# OpenDeck-r2_0_1.net
KiCad netlist of a schematic drawn in EAGLE
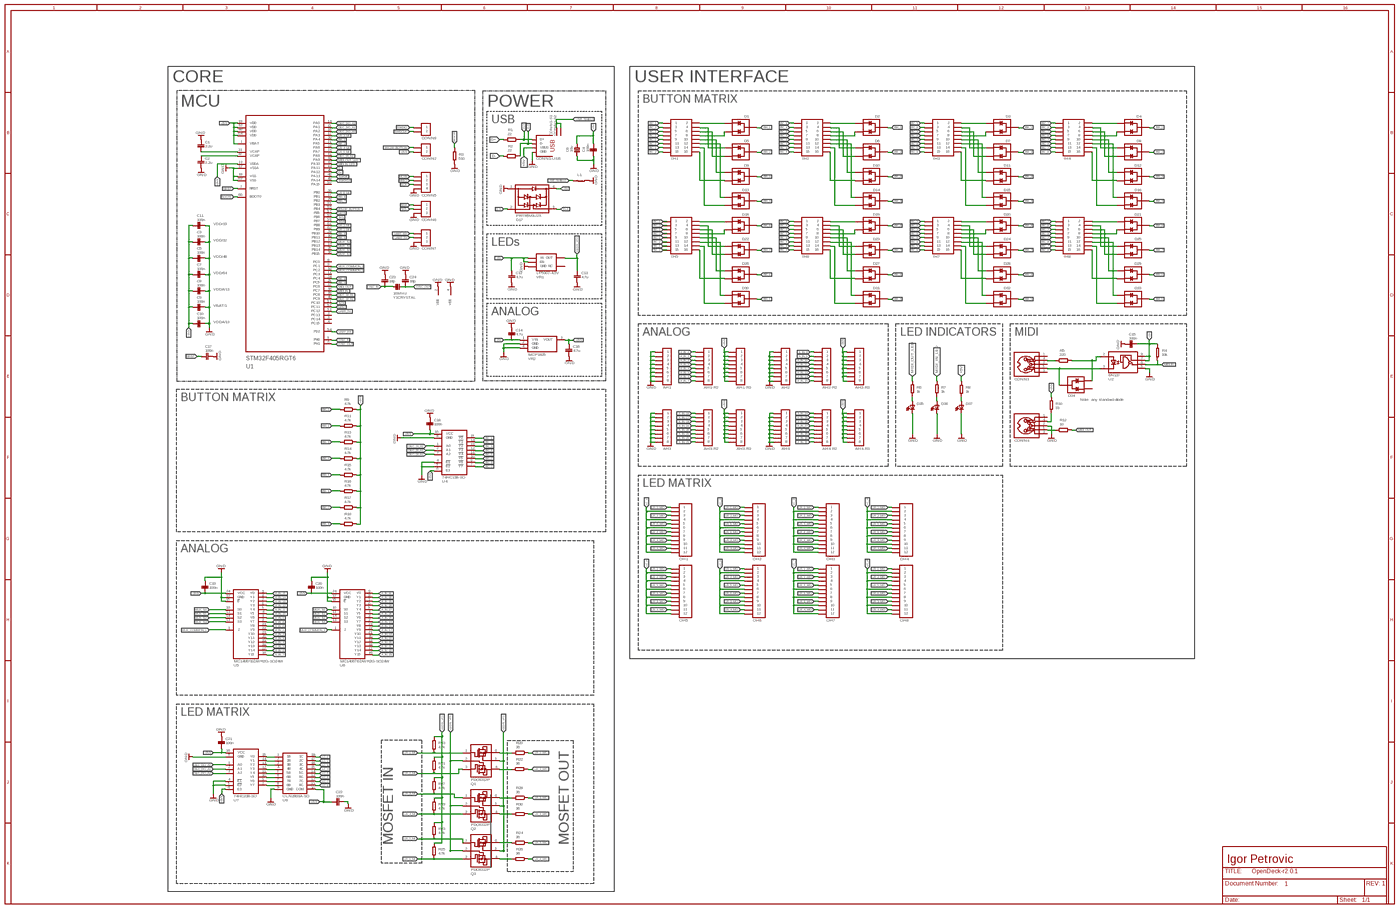
[diagram p0: schematic, sheet 1, overview]
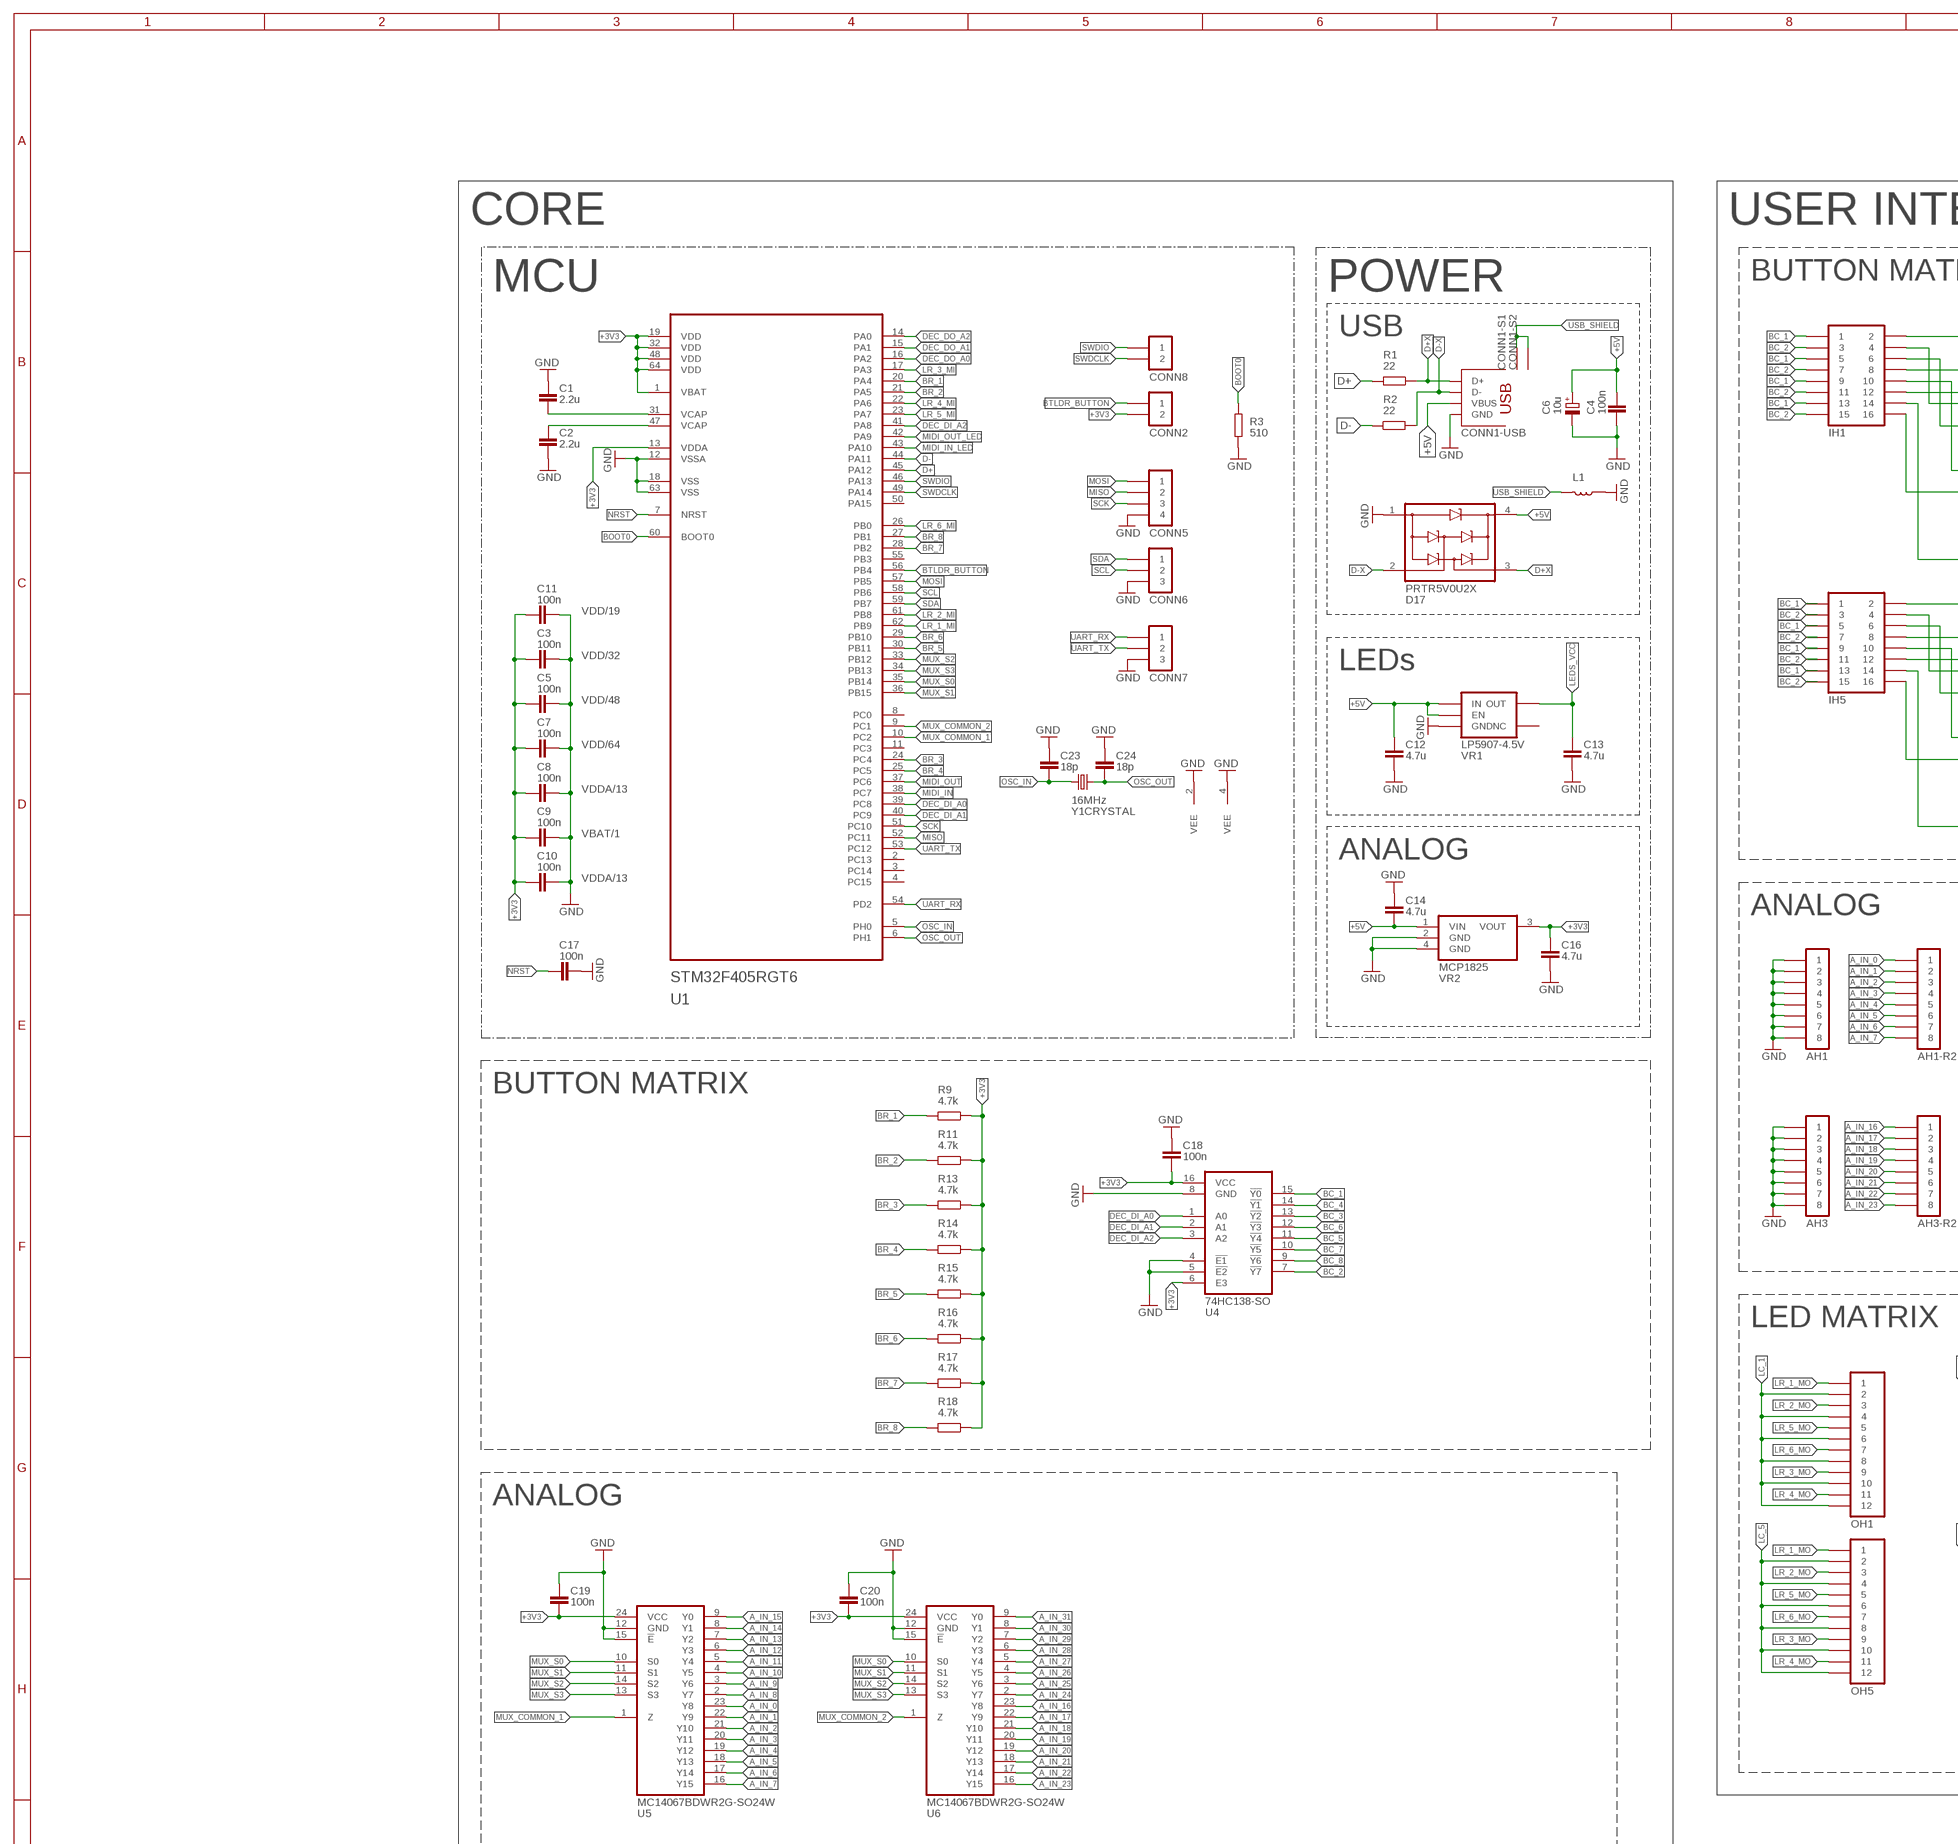
[diagram p1: schematic, sheet 1, part 1 of 4]
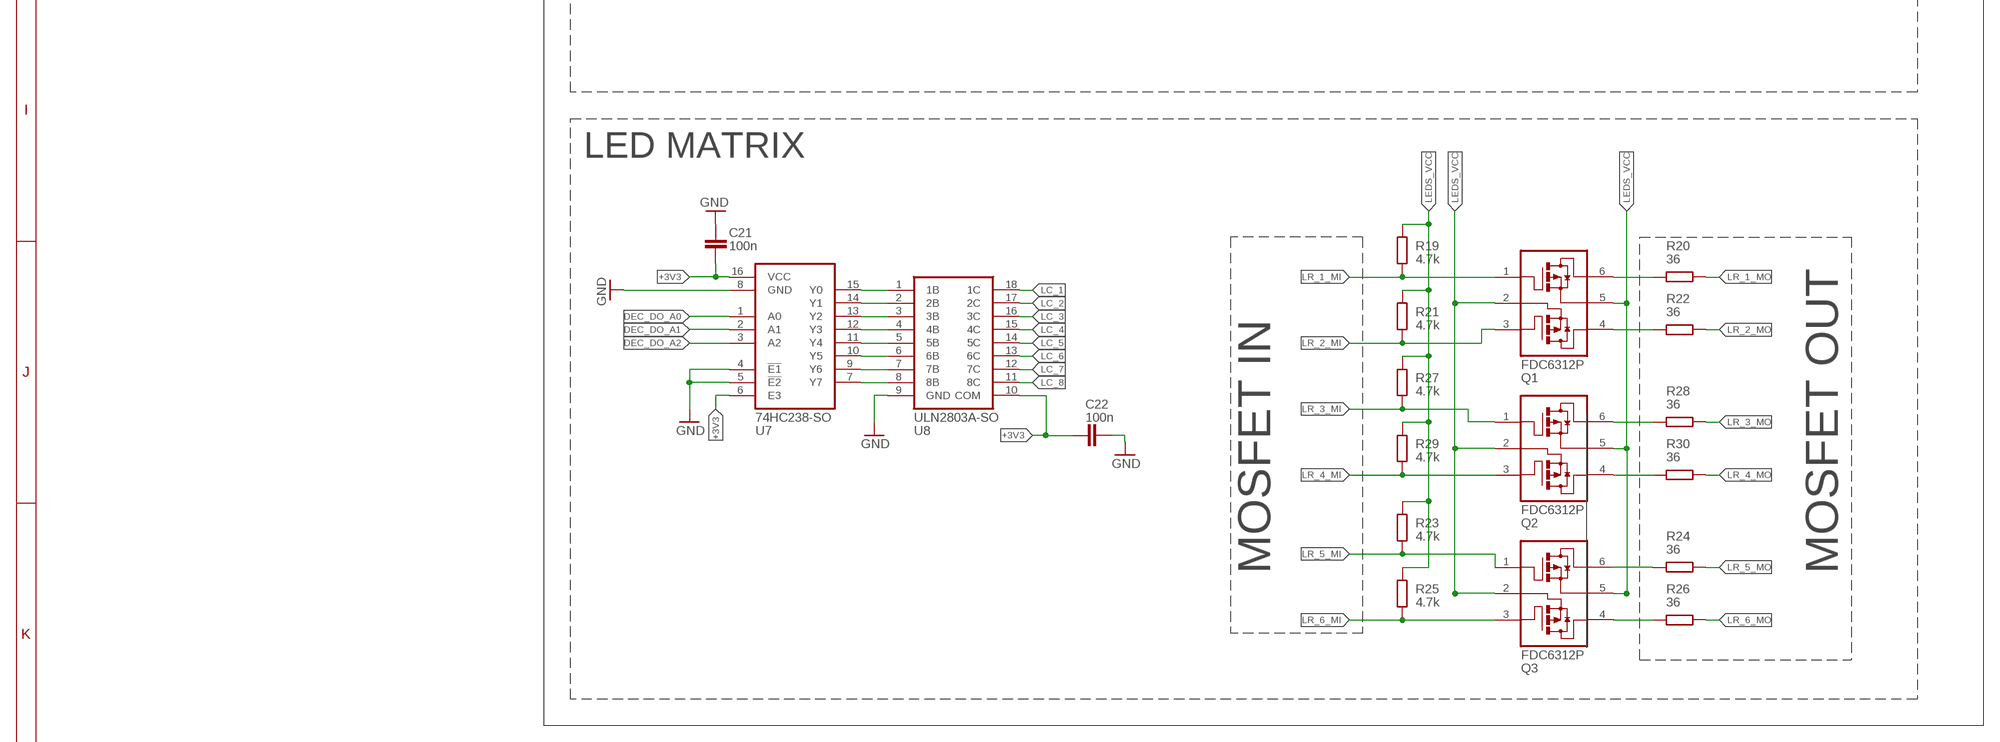
[diagram p2: schematic, sheet 1, part 2 of 4]
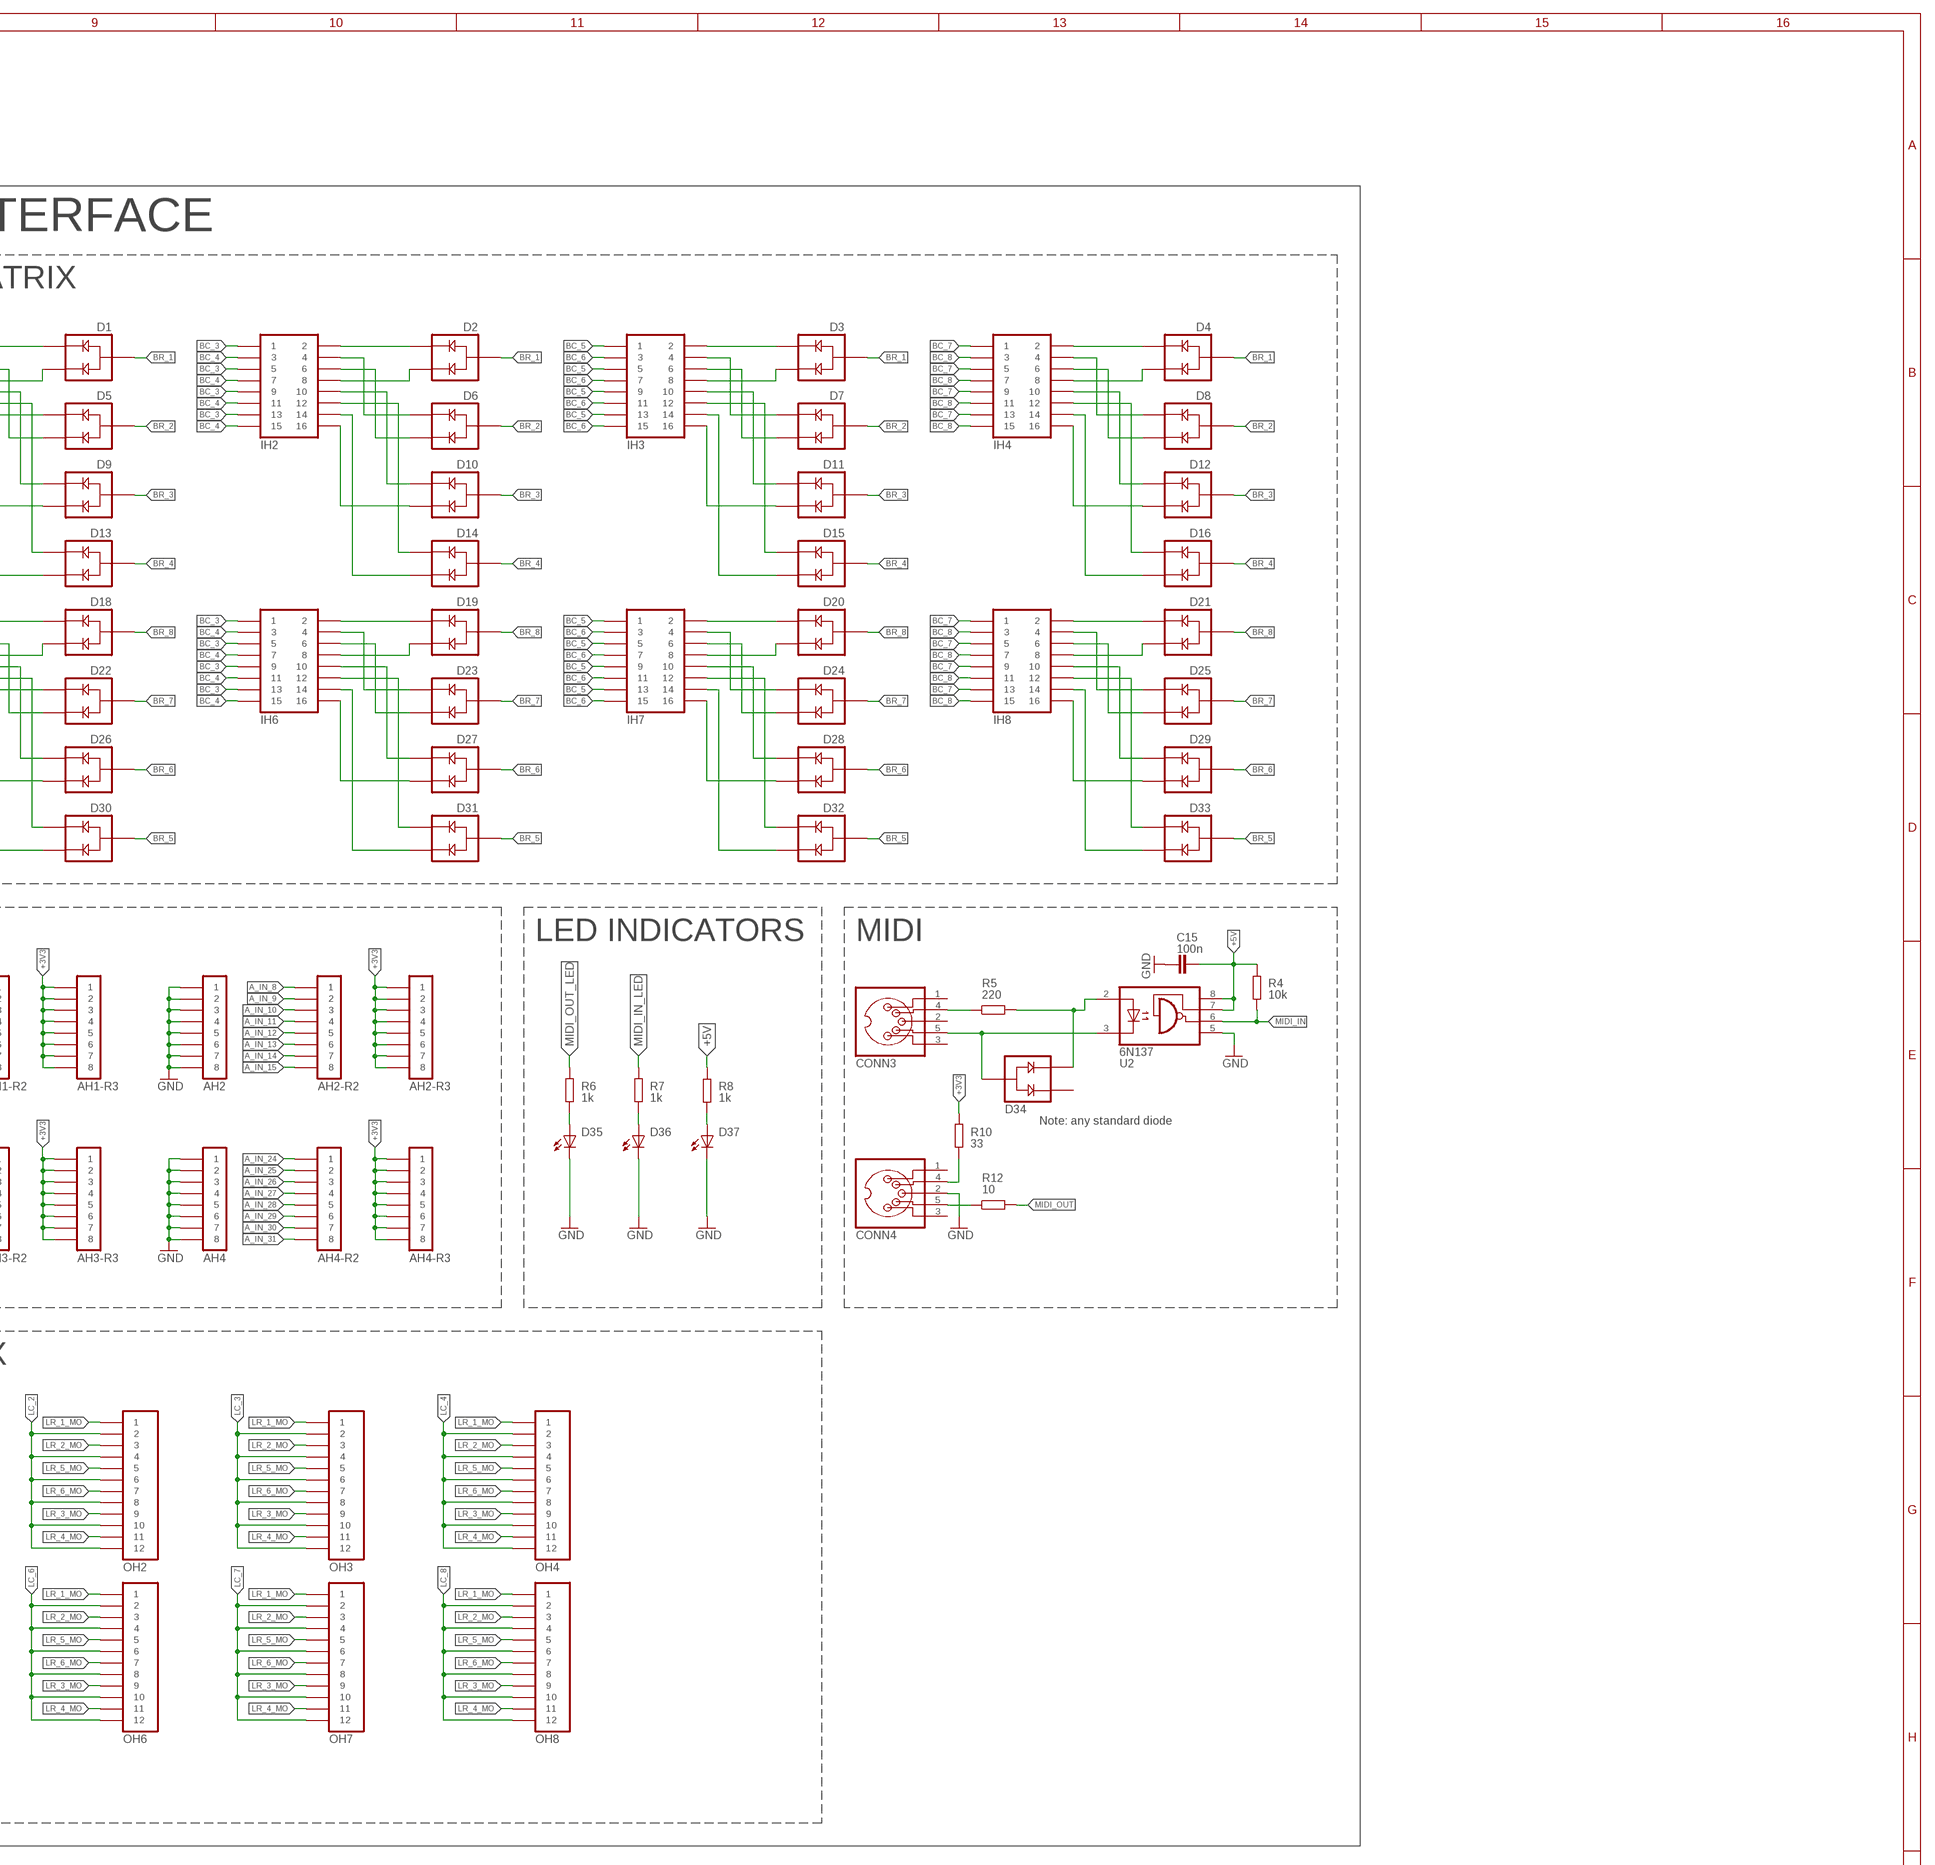
[diagram p3: schematic, sheet 1, part 3 of 4]
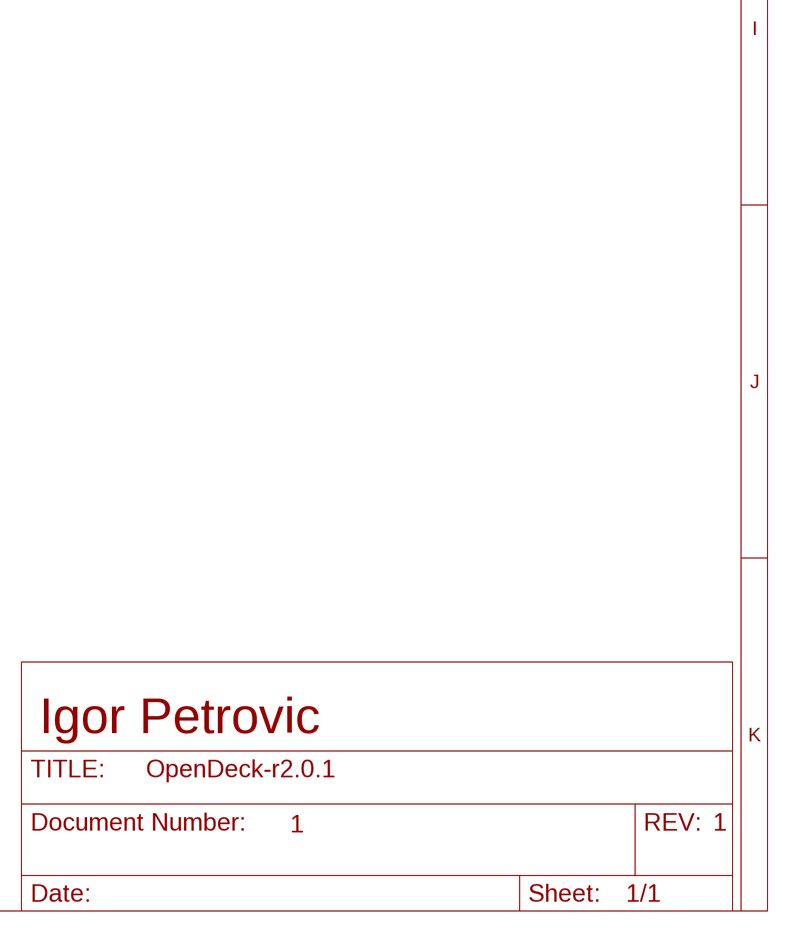
[diagram p4: schematic, sheet 1, part 4 of 4]

(export (version "E")
  (design (tool "Eeschema 10.0.6"))
  (components
    (comp (ref "AH1")
      (value "PINHD-3X08")
      (footprint "eagle-import:3X08-2.54")
      (libsource (lib "eagle-import") (part "PINHD-3X08"))
    )
    (comp (ref "AH2")
      (value "PINHD-3X08")
      (footprint "eagle-import:3X08-2.54")
      (libsource (lib "eagle-import") (part "PINHD-3X08"))
    )
    (comp (ref "AH3")
      (value "PINHD-3X08")
      (footprint "eagle-import:3X08-2.54")
      (libsource (lib "eagle-import") (part "PINHD-3X08"))
    )
    (comp (ref "AH4")
      (value "PINHD-3X08")
      (footprint "eagle-import:3X08-2.54")
      (libsource (lib "eagle-import") (part "PINHD-3X08"))
    )
    (comp (ref "C1")
      (value "2.2u")
      (footprint "eagle-import:C0402")
      (libsource (lib "eagle-import") (part "CAPACITOR-0402"))
    )
    (comp (ref "C2")
      (value "2.2u")
      (footprint "eagle-import:C0402")
      (libsource (lib "eagle-import") (part "CAPACITOR-0402"))
    )
    (comp (ref "C3")
      (value "100n")
      (footprint "eagle-import:C0402")
      (libsource (lib "eagle-import") (part "CAPACITOR-0402"))
    )
    (comp (ref "C4")
      (value "100n")
      (footprint "eagle-import:C0402")
      (libsource (lib "eagle-import") (part "CAPACITOR-0402"))
    )
    (comp (ref "C5")
      (value "100n")
      (footprint "eagle-import:C0402")
      (libsource (lib "eagle-import") (part "CAPACITOR-0402"))
    )
    (comp (ref "C6")
      (value "10u")
      (footprint "eagle-import:153CLV-0405")
      (fields (field (name "MANUFACTURER") "Multicomp") (field (name "MPN") "MCVVT016M100CA1L"))
      (libsource (lib "eagle-import") (part "ELECTROLYTIC_CAPACITOR-CLV-040516V"))
    )
    (comp (ref "C7")
      (value "100n")
      (footprint "eagle-import:C0402")
      (libsource (lib "eagle-import") (part "CAPACITOR-0402"))
    )
    (comp (ref "C8")
      (value "100n")
      (footprint "eagle-import:C0402")
      (libsource (lib "eagle-import") (part "CAPACITOR-0402"))
    )
    (comp (ref "C9")
      (value "100n")
      (footprint "eagle-import:C0402")
      (libsource (lib "eagle-import") (part "CAPACITOR-0402"))
    )
    (comp (ref "C10")
      (value "100n")
      (footprint "eagle-import:C0402")
      (libsource (lib "eagle-import") (part "CAPACITOR-0402"))
    )
    (comp (ref "C11")
      (value "100n")
      (footprint "eagle-import:C0402")
      (libsource (lib "eagle-import") (part "CAPACITOR-0402"))
    )
    (comp (ref "C12")
      (value "4.7u")
      (footprint "eagle-import:C0402")
      (libsource (lib "eagle-import") (part "CAPACITOR-0402"))
    )
    (comp (ref "C13")
      (value "4.7u")
      (footprint "eagle-import:C0402")
      (libsource (lib "eagle-import") (part "CAPACITOR-0402"))
    )
    (comp (ref "C14")
      (value "4.7u")
      (footprint "eagle-import:C0402")
      (libsource (lib "eagle-import") (part "CAPACITOR-0402"))
    )
    (comp (ref "C15")
      (value "100n")
      (footprint "eagle-import:C0402")
      (libsource (lib "eagle-import") (part "CAPACITOR-0402"))
    )
    (comp (ref "C16")
      (value "4.7u")
      (footprint "eagle-import:C0402")
      (libsource (lib "eagle-import") (part "CAPACITOR-0402"))
    )
    (comp (ref "C17")
      (value "100n")
      (footprint "eagle-import:C0402")
      (libsource (lib "eagle-import") (part "CAPACITOR-0402"))
    )
    (comp (ref "C18")
      (value "100n")
      (footprint "eagle-import:C0402")
      (libsource (lib "eagle-import") (part "CAPACITOR-0402"))
    )
    (comp (ref "C19")
      (value "100n")
      (footprint "eagle-import:C0402")
      (libsource (lib "eagle-import") (part "CAPACITOR-0402"))
    )
    (comp (ref "C20")
      (value "100n")
      (footprint "eagle-import:C0402")
      (libsource (lib "eagle-import") (part "CAPACITOR-0402"))
    )
    (comp (ref "C21")
      (value "100n")
      (footprint "eagle-import:C0402")
      (libsource (lib "eagle-import") (part "CAPACITOR-0402"))
    )
    (comp (ref "C22")
      (value "100n")
      (footprint "eagle-import:C0402")
      (libsource (lib "eagle-import") (part "CAPACITOR-0402"))
    )
    (comp (ref "C23")
      (value "18p")
      (footprint "eagle-import:C0402")
      (libsource (lib "eagle-import") (part "CAPACITOR-0402"))
    )
    (comp (ref "C24")
      (value "18p")
      (footprint "eagle-import:C0402")
      (libsource (lib "eagle-import") (part "CAPACITOR-0402"))
    )
    (comp (ref "CONN1")
      (value "USB-H")
      (footprint "eagle-import:USB-B-PTH")
      (libsource (lib "eagle-import") (part "USB-H"))
    )
    (comp (ref "CONN2")
      (value "PINHD-1X02-TH-2.54MM")
      (footprint "eagle-import:1X02-2.54-V")
      (libsource (lib "eagle-import") (part "PINHD-1X02-TH-2.54MM"))
    )
    (comp (ref "CONN3")
      (value "MIDI_CONN-STD")
      (footprint "eagle-import:DIN5_SUPPORT")
      (libsource (lib "eagle-import") (part "MIDI_CONN-STD"))
    )
    (comp (ref "CONN4")
      (value "MIDI_CONN-STD")
      (footprint "eagle-import:DIN5_SUPPORT")
      (libsource (lib "eagle-import") (part "MIDI_CONN-STD"))
    )
    (comp (ref "CONN5")
      (value "PINHD-1X04-TH-2.54MM")
      (footprint "eagle-import:1X04-2.54")
      (libsource (lib "eagle-import") (part "PINHD-1X04-TH-2.54MM"))
    )
    (comp (ref "CONN6")
      (value "PINHD-1X03-TH-2.54MM")
      (footprint "eagle-import:1X03-2.54-V")
      (libsource (lib "eagle-import") (part "PINHD-1X03-TH-2.54MM"))
    )
    (comp (ref "CONN7")
      (value "PINHD-1X03-TH-2.54MM")
      (footprint "eagle-import:1X03-2.54-V")
      (libsource (lib "eagle-import") (part "PINHD-1X03-TH-2.54MM"))
    )
    (comp (ref "CONN8")
      (value "PINHD-1X02-TH-2.54MM")
      (footprint "eagle-import:1X02-2.54-V")
      (libsource (lib "eagle-import") (part "PINHD-1X02-TH-2.54MM"))
    )
    (comp (ref "D1")
      (value "BAW56")
      (footprint "eagle-import:SOT23")
      (fields (field (name "MANUFACTURER") "Multicomp") (field (name "MPN") "BAW56-7-F"))
      (libsource (lib "eagle-import") (part "BAW56"))
    )
    (comp (ref "D2")
      (value "BAW56")
      (footprint "eagle-import:SOT23")
      (fields (field (name "MANUFACTURER") "Multicomp") (field (name "MPN") "BAW56-7-F"))
      (libsource (lib "eagle-import") (part "BAW56"))
    )
    (comp (ref "D3")
      (value "BAW56")
      (footprint "eagle-import:SOT23")
      (fields (field (name "MANUFACTURER") "Multicomp") (field (name "MPN") "BAW56-7-F"))
      (libsource (lib "eagle-import") (part "BAW56"))
    )
    (comp (ref "D4")
      (value "BAW56")
      (footprint "eagle-import:SOT23")
      (fields (field (name "MANUFACTURER") "Multicomp") (field (name "MPN") "BAW56-7-F"))
      (libsource (lib "eagle-import") (part "BAW56"))
    )
    (comp (ref "D5")
      (value "BAW56")
      (footprint "eagle-import:SOT23")
      (fields (field (name "MANUFACTURER") "Multicomp") (field (name "MPN") "BAW56-7-F"))
      (libsource (lib "eagle-import") (part "BAW56"))
    )
    (comp (ref "D6")
      (value "BAW56")
      (footprint "eagle-import:SOT23")
      (fields (field (name "MANUFACTURER") "Multicomp") (field (name "MPN") "BAW56-7-F"))
      (libsource (lib "eagle-import") (part "BAW56"))
    )
    (comp (ref "D7")
      (value "BAW56")
      (footprint "eagle-import:SOT23")
      (fields (field (name "MANUFACTURER") "Multicomp") (field (name "MPN") "BAW56-7-F"))
      (libsource (lib "eagle-import") (part "BAW56"))
    )
    (comp (ref "D8")
      (value "BAW56")
      (footprint "eagle-import:SOT23")
      (fields (field (name "MANUFACTURER") "Multicomp") (field (name "MPN") "BAW56-7-F"))
      (libsource (lib "eagle-import") (part "BAW56"))
    )
    (comp (ref "D9")
      (value "BAW56")
      (footprint "eagle-import:SOT23")
      (fields (field (name "MANUFACTURER") "Multicomp") (field (name "MPN") "BAW56-7-F"))
      (libsource (lib "eagle-import") (part "BAW56"))
    )
    (comp (ref "D10")
      (value "BAW56")
      (footprint "eagle-import:SOT23")
      (fields (field (name "MANUFACTURER") "Multicomp") (field (name "MPN") "BAW56-7-F"))
      (libsource (lib "eagle-import") (part "BAW56"))
    )
    (comp (ref "D11")
      (value "BAW56")
      (footprint "eagle-import:SOT23")
      (fields (field (name "MANUFACTURER") "Multicomp") (field (name "MPN") "BAW56-7-F"))
      (libsource (lib "eagle-import") (part "BAW56"))
    )
    (comp (ref "D12")
      (value "BAW56")
      (footprint "eagle-import:SOT23")
      (fields (field (name "MANUFACTURER") "Multicomp") (field (name "MPN") "BAW56-7-F"))
      (libsource (lib "eagle-import") (part "BAW56"))
    )
    (comp (ref "D13")
      (value "BAW56")
      (footprint "eagle-import:SOT23")
      (fields (field (name "MANUFACTURER") "Multicomp") (field (name "MPN") "BAW56-7-F"))
      (libsource (lib "eagle-import") (part "BAW56"))
    )
    (comp (ref "D14")
      (value "BAW56")
      (footprint "eagle-import:SOT23")
      (fields (field (name "MANUFACTURER") "Multicomp") (field (name "MPN") "BAW56-7-F"))
      (libsource (lib "eagle-import") (part "BAW56"))
    )
    (comp (ref "D15")
      (value "BAW56")
      (footprint "eagle-import:SOT23")
      (fields (field (name "MANUFACTURER") "Multicomp") (field (name "MPN") "BAW56-7-F"))
      (libsource (lib "eagle-import") (part "BAW56"))
    )
    (comp (ref "D16")
      (value "BAW56")
      (footprint "eagle-import:SOT23")
      (fields (field (name "MANUFACTURER") "Multicomp") (field (name "MPN") "BAW56-7-F"))
      (libsource (lib "eagle-import") (part "BAW56"))
    )
    (comp (ref "D17")
      (value "PRTR5V0U2X")
      (footprint "eagle-import:SOT143")
      (fields (field (name "MANUFACTURER") "Nexperia"))
      (libsource (lib "eagle-import") (part "PRTR5V0U2X"))
    )
    (comp (ref "D18")
      (value "BAW56")
      (footprint "eagle-import:SOT23")
      (fields (field (name "MANUFACTURER") "Multicomp") (field (name "MPN") "BAW56-7-F"))
      (libsource (lib "eagle-import") (part "BAW56"))
    )
    (comp (ref "D19")
      (value "BAW56")
      (footprint "eagle-import:SOT23")
      (fields (field (name "MANUFACTURER") "Multicomp") (field (name "MPN") "BAW56-7-F"))
      (libsource (lib "eagle-import") (part "BAW56"))
    )
    (comp (ref "D20")
      (value "BAW56")
      (footprint "eagle-import:SOT23")
      (fields (field (name "MANUFACTURER") "Multicomp") (field (name "MPN") "BAW56-7-F"))
      (libsource (lib "eagle-import") (part "BAW56"))
    )
    (comp (ref "D21")
      (value "BAW56")
      (footprint "eagle-import:SOT23")
      (fields (field (name "MANUFACTURER") "Multicomp") (field (name "MPN") "BAW56-7-F"))
      (libsource (lib "eagle-import") (part "BAW56"))
    )
    (comp (ref "D22")
      (value "BAW56")
      (footprint "eagle-import:SOT23")
      (fields (field (name "MANUFACTURER") "Multicomp") (field (name "MPN") "BAW56-7-F"))
      (libsource (lib "eagle-import") (part "BAW56"))
    )
    (comp (ref "D23")
      (value "BAW56")
      (footprint "eagle-import:SOT23")
      (fields (field (name "MANUFACTURER") "Multicomp") (field (name "MPN") "BAW56-7-F"))
      (libsource (lib "eagle-import") (part "BAW56"))
    )
    (comp (ref "D24")
      (value "BAW56")
      (footprint "eagle-import:SOT23")
      (fields (field (name "MANUFACTURER") "Multicomp") (field (name "MPN") "BAW56-7-F"))
      (libsource (lib "eagle-import") (part "BAW56"))
    )
    (comp (ref "D25")
      (value "BAW56")
      (footprint "eagle-import:SOT23")
      (fields (field (name "MANUFACTURER") "Multicomp") (field (name "MPN") "BAW56-7-F"))
      (libsource (lib "eagle-import") (part "BAW56"))
    )
    (comp (ref "D26")
      (value "BAW56")
      (footprint "eagle-import:SOT23")
      (fields (field (name "MANUFACTURER") "Multicomp") (field (name "MPN") "BAW56-7-F"))
      (libsource (lib "eagle-import") (part "BAW56"))
    )
    (comp (ref "D27")
      (value "BAW56")
      (footprint "eagle-import:SOT23")
      (fields (field (name "MANUFACTURER") "Multicomp") (field (name "MPN") "BAW56-7-F"))
      (libsource (lib "eagle-import") (part "BAW56"))
    )
    (comp (ref "D28")
      (value "BAW56")
      (footprint "eagle-import:SOT23")
      (fields (field (name "MANUFACTURER") "Multicomp") (field (name "MPN") "BAW56-7-F"))
      (libsource (lib "eagle-import") (part "BAW56"))
    )
    (comp (ref "D29")
      (value "BAW56")
      (footprint "eagle-import:SOT23")
      (fields (field (name "MANUFACTURER") "Multicomp") (field (name "MPN") "BAW56-7-F"))
      (libsource (lib "eagle-import") (part "BAW56"))
    )
    (comp (ref "D30")
      (value "BAW56")
      (footprint "eagle-import:SOT23")
      (fields (field (name "MANUFACTURER") "Multicomp") (field (name "MPN") "BAW56-7-F"))
      (libsource (lib "eagle-import") (part "BAW56"))
    )
    (comp (ref "D31")
      (value "BAW56")
      (footprint "eagle-import:SOT23")
      (fields (field (name "MANUFACTURER") "Multicomp") (field (name "MPN") "BAW56-7-F"))
      (libsource (lib "eagle-import") (part "BAW56"))
    )
    (comp (ref "D32")
      (value "BAW56")
      (footprint "eagle-import:SOT23")
      (fields (field (name "MANUFACTURER") "Multicomp") (field (name "MPN") "BAW56-7-F"))
      (libsource (lib "eagle-import") (part "BAW56"))
    )
    (comp (ref "D33")
      (value "BAW56")
      (footprint "eagle-import:SOT23")
      (fields (field (name "MANUFACTURER") "Multicomp") (field (name "MPN") "BAW56-7-F"))
      (libsource (lib "eagle-import") (part "BAW56"))
    )
    (comp (ref "D34")
      (value "BAW56")
      (footprint "eagle-import:SOT23")
      (fields (field (name "MANUFACTURER") "Multicomp") (field (name "MPN") "BAW56-7-F"))
      (libsource (lib "eagle-import") (part "BAW56"))
    )
    (comp (ref "D35")
      (value "Red")
      (footprint "eagle-import:0805_LED")
      (libsource (lib "eagle-import") (part "LED-0805"))
    )
    (comp (ref "D36")
      (value "Yellow")
      (footprint "eagle-import:0805_LED")
      (libsource (lib "eagle-import") (part "LED-0805"))
    )
    (comp (ref "D37")
      (value "Green")
      (footprint "eagle-import:0805_LED")
      (libsource (lib "eagle-import") (part "LED-0805"))
    )
    (comp (ref "IH1")
      (value "PINHD-2X08-TH-2.54MM")
      (footprint "eagle-import:2X08-2.54")
      (libsource (lib "eagle-import") (part "PINHD-2X08-TH-2.54MM"))
    )
    (comp (ref "IH2")
      (value "PINHD-2X08-TH-2.54MM")
      (footprint "eagle-import:2X08-2.54")
      (libsource (lib "eagle-import") (part "PINHD-2X08-TH-2.54MM"))
    )
    (comp (ref "IH3")
      (value "PINHD-2X08-TH-2.54MM")
      (footprint "eagle-import:2X08-2.54")
      (libsource (lib "eagle-import") (part "PINHD-2X08-TH-2.54MM"))
    )
    (comp (ref "IH4")
      (value "PINHD-2X08-TH-2.54MM")
      (footprint "eagle-import:2X08-2.54")
      (libsource (lib "eagle-import") (part "PINHD-2X08-TH-2.54MM"))
    )
    (comp (ref "IH5")
      (value "PINHD-2X08-TH-2.54MM")
      (footprint "eagle-import:2X08-2.54")
      (libsource (lib "eagle-import") (part "PINHD-2X08-TH-2.54MM"))
    )
    (comp (ref "IH6")
      (value "PINHD-2X08-TH-2.54MM")
      (footprint "eagle-import:2X08-2.54")
      (libsource (lib "eagle-import") (part "PINHD-2X08-TH-2.54MM"))
    )
    (comp (ref "IH7")
      (value "PINHD-2X08-TH-2.54MM")
      (footprint "eagle-import:2X08-2.54")
      (libsource (lib "eagle-import") (part "PINHD-2X08-TH-2.54MM"))
    )
    (comp (ref "IH8")
      (value "PINHD-2X08-TH-2.54MM")
      (footprint "eagle-import:2X08-2.54")
      (libsource (lib "eagle-import") (part "PINHD-2X08-TH-2.54MM"))
    )
    (comp (ref "L1")
      (value "FERRITE_BEAD-BLM21PG221SN1D")
      (footprint "eagle-import:L0805")
      (fields (field (name "MANUFACTURER") "Murata") (field (name "MPN") "BLM21PG221SN1D"))
      (libsource (lib "eagle-import") (part "FERRITE_BEAD-BLM21PG221SN1D"))
    )
    (comp (ref "OH1")
      (value "PINHD-2X06-TH-2.54MM")
      (footprint "eagle-import:2X06-2.54-V")
      (libsource (lib "eagle-import") (part "PINHD-2X06-TH-2.54MM"))
    )
    (comp (ref "OH2")
      (value "PINHD-2X06-TH-2.54MM")
      (footprint "eagle-import:2X06-2.54-V")
      (libsource (lib "eagle-import") (part "PINHD-2X06-TH-2.54MM"))
    )
    (comp (ref "OH3")
      (value "PINHD-2X06-TH-2.54MM")
      (footprint "eagle-import:2X06-2.54-V")
      (libsource (lib "eagle-import") (part "PINHD-2X06-TH-2.54MM"))
    )
    (comp (ref "OH4")
      (value "PINHD-2X06-TH-2.54MM")
      (footprint "eagle-import:2X06-2.54-V")
      (libsource (lib "eagle-import") (part "PINHD-2X06-TH-2.54MM"))
    )
    (comp (ref "OH5")
      (value "PINHD-2X06-TH-2.54MM")
      (footprint "eagle-import:2X06-2.54-V")
      (libsource (lib "eagle-import") (part "PINHD-2X06-TH-2.54MM"))
    )
    (comp (ref "OH6")
      (value "PINHD-2X06-TH-2.54MM")
      (footprint "eagle-import:2X06-2.54-V")
      (libsource (lib "eagle-import") (part "PINHD-2X06-TH-2.54MM"))
    )
    (comp (ref "OH7")
      (value "PINHD-2X06-TH-2.54MM")
      (footprint "eagle-import:2X06-2.54-V")
      (libsource (lib "eagle-import") (part "PINHD-2X06-TH-2.54MM"))
    )
    (comp (ref "OH8")
      (value "PINHD-2X06-TH-2.54MM")
      (footprint "eagle-import:2X06-2.54-V")
      (libsource (lib "eagle-import") (part "PINHD-2X06-TH-2.54MM"))
    )
    (comp (ref "Q1")
      (value "FDC6312P")
      (footprint "eagle-import:SSOT6")
      (fields (field (name "MANUFACTURER") "ON Semiconductor"))
      (libsource (lib "eagle-import") (part "FDC6312P"))
    )
    (comp (ref "Q2")
      (value "FDC6312P")
      (footprint "eagle-import:SSOT6")
      (fields (field (name "MANUFACTURER") "ON Semiconductor"))
      (libsource (lib "eagle-import") (part "FDC6312P"))
    )
    (comp (ref "Q3")
      (value "FDC6312P")
      (footprint "eagle-import:SSOT6")
      (fields (field (name "MANUFACTURER") "ON Semiconductor"))
      (libsource (lib "eagle-import") (part "FDC6312P"))
    )
    (comp (ref "R1")
      (value "22")
      (footprint "eagle-import:R0402")
      (libsource (lib "eagle-import") (part "RESISTOR-0402"))
    )
    (comp (ref "R2")
      (value "22")
      (footprint "eagle-import:R0402")
      (libsource (lib "eagle-import") (part "RESISTOR-0402"))
    )
    (comp (ref "R3")
      (value "510")
      (footprint "eagle-import:R0402")
      (libsource (lib "eagle-import") (part "RESISTOR-0402"))
    )
    (comp (ref "R4")
      (value "10k")
      (footprint "eagle-import:R0402")
      (libsource (lib "eagle-import") (part "RESISTOR-0402"))
    )
    (comp (ref "R5")
      (value "220")
      (footprint "eagle-import:R0402")
      (libsource (lib "eagle-import") (part "RESISTOR-0402"))
    )
    (comp (ref "R6")
      (value "1k")
      (footprint "eagle-import:R0402")
      (libsource (lib "eagle-import") (part "RESISTOR-0402"))
    )
    (comp (ref "R7")
      (value "1k")
      (footprint "eagle-import:R0402")
      (libsource (lib "eagle-import") (part "RESISTOR-0402"))
    )
    (comp (ref "R8")
      (value "1k")
      (footprint "eagle-import:R0402")
      (libsource (lib "eagle-import") (part "RESISTOR-0402"))
    )
    (comp (ref "R9")
      (value "4.7k")
      (footprint "eagle-import:R0402")
      (libsource (lib "eagle-import") (part "RESISTOR-0402"))
    )
    (comp (ref "R10")
      (value "33")
      (footprint "eagle-import:R0402")
      (libsource (lib "eagle-import") (part "RESISTOR-0402"))
    )
    (comp (ref "R11")
      (value "4.7k")
      (footprint "eagle-import:R0402")
      (libsource (lib "eagle-import") (part "RESISTOR-0402"))
    )
    (comp (ref "R12")
      (value "10")
      (footprint "eagle-import:R0402")
      (libsource (lib "eagle-import") (part "RESISTOR-0402"))
    )
    (comp (ref "R13")
      (value "4.7k")
      (footprint "eagle-import:R0402")
      (libsource (lib "eagle-import") (part "RESISTOR-0402"))
    )
    (comp (ref "R14")
      (value "4.7k")
      (footprint "eagle-import:R0402")
      (libsource (lib "eagle-import") (part "RESISTOR-0402"))
    )
    (comp (ref "R15")
      (value "4.7k")
      (footprint "eagle-import:R0402")
      (libsource (lib "eagle-import") (part "RESISTOR-0402"))
    )
    (comp (ref "R16")
      (value "4.7k")
      (footprint "eagle-import:R0402")
      (libsource (lib "eagle-import") (part "RESISTOR-0402"))
    )
    (comp (ref "R17")
      (value "4.7k")
      (footprint "eagle-import:R0402")
      (libsource (lib "eagle-import") (part "RESISTOR-0402"))
    )
    (comp (ref "R18")
      (value "4.7k")
      (footprint "eagle-import:R0402")
      (libsource (lib "eagle-import") (part "RESISTOR-0402"))
    )
    (comp (ref "R19")
      (value "4.7k")
      (footprint "eagle-import:R0402")
      (libsource (lib "eagle-import") (part "RESISTOR-0402"))
    )
    (comp (ref "R20")
      (value "36")
      (footprint "eagle-import:R0402")
      (libsource (lib "eagle-import") (part "RESISTOR-0402"))
    )
    (comp (ref "R21")
      (value "4.7k")
      (footprint "eagle-import:R0402")
      (libsource (lib "eagle-import") (part "RESISTOR-0402"))
    )
    (comp (ref "R22")
      (value "36")
      (footprint "eagle-import:R0402")
      (libsource (lib "eagle-import") (part "RESISTOR-0402"))
    )
    (comp (ref "R23")
      (value "4.7k")
      (footprint "eagle-import:R0402")
      (libsource (lib "eagle-import") (part "RESISTOR-0402"))
    )
    (comp (ref "R24")
      (value "36")
      (footprint "eagle-import:R0402")
      (libsource (lib "eagle-import") (part "RESISTOR-0402"))
    )
    (comp (ref "R25")
      (value "4.7k")
      (footprint "eagle-import:R0402")
      (libsource (lib "eagle-import") (part "RESISTOR-0402"))
    )
    (comp (ref "R26")
      (value "36")
      (footprint "eagle-import:R0402")
      (libsource (lib "eagle-import") (part "RESISTOR-0402"))
    )
    (comp (ref "R27")
      (value "4.7k")
      (footprint "eagle-import:R0402")
      (libsource (lib "eagle-import") (part "RESISTOR-0402"))
    )
    (comp (ref "R28")
      (value "36")
      (footprint "eagle-import:R0402")
      (libsource (lib "eagle-import") (part "RESISTOR-0402"))
    )
    (comp (ref "R29")
      (value "4.7k")
      (footprint "eagle-import:R0402")
      (libsource (lib "eagle-import") (part "RESISTOR-0402"))
    )
    (comp (ref "R30")
      (value "36")
      (footprint "eagle-import:R0402")
      (libsource (lib "eagle-import") (part "RESISTOR-0402"))
    )
    (comp (ref "U1")
      (value "STM32F405RGT6")
      (footprint "eagle-import:TQFP-64-10X10")
      (fields (field (name "MANUFACTURER") "ST Microelectronics"))
      (libsource (lib "eagle-import") (part "STM32F405RGT6"))
    )
    (comp (ref "U2")
      (value "6N137")
      (footprint "eagle-import:DIL08")
      (fields (field (name "MANUFACTURER") "Vishay"))
      (libsource (lib "eagle-import") (part "6N137"))
    )
    (comp (ref "U4")
      (value "74HC138-SO")
      (footprint "eagle-import:SO16")
      (fields (field (name "MANUFACTURER") "Nexperia") (field (name "MPN") "74HC138D"))
      (libsource (lib "eagle-import") (part "74138-SOHC"))
    )
    (comp (ref "U5")
      (value "MC14067BDWR2G-SO24W")
      (footprint "eagle-import:SO24-W")
      (fields (field (name "MANUFACTURER") "ON Semiconductor") (field (name "MPN") "MC14067BDWR2G"))
      (libsource (lib "eagle-import") (part "MC14067BDWR2G-SO24W"))
    )
    (comp (ref "U6")
      (value "MC14067BDWR2G-SO24W")
      (footprint "eagle-import:SO24-W")
      (fields (field (name "MANUFACTURER") "ON Semiconductor") (field (name "MPN") "MC14067BDWR2G"))
      (libsource (lib "eagle-import") (part "MC14067BDWR2G-SO24W"))
    )
    (comp (ref "U7")
      (value "74HC238-SO")
      (footprint "eagle-import:SO16")
      (fields (field (name "MANUFACTURER") "Nexperia") (field (name "MPN") "74HC238D"))
      (libsource (lib "eagle-import") (part "74238-SOHC"))
    )
    (comp (ref "U8")
      (value "ULN2803A-SO")
      (footprint "eagle-import:SO18")
      (fields (field (name "MANUFACTURER") "Texas Instruments") (field (name "MPN") "ULN2803ADWR"))
      (libsource (lib "eagle-import") (part "ULN2803A-SO"))
    )
    (comp (ref "VR1")
      (value "LP5907-4.5V")
      (footprint "eagle-import:SOT23-5")
      (fields (field (name "MANUFACTURER") "Texas Instruments") (field (name "MPN") "LP5907MFX-4.5/NOPB"))
      (libsource (lib "eagle-import") (part "LP5907-4.5V"))
    )
    (comp (ref "VR2")
      (value "MCP1825")
      (footprint "eagle-import:SOT223")
      (fields (field (name "MANUFACTURER") "Microchip") (field (name "MPN") "MCP1825S-3302E/DB"))
      (libsource (lib "eagle-import") (part "MCP1825"))
    )
    (comp (ref "Y1")
      (value "16MHz")
      (footprint "eagle-import:CRYSTAL-SMD-2.5X2")
      (fields (field (name "MANUFACTURER") "TXC") (field (name "MPN") "8Z-16.000MEEQ-T"))
      (libsource (lib "eagle-import") (part "CRYSTAL-4P-SMD-2.5X2"))
    )
  )
  (nets
    (net (code "1") (name "+3V3") (class "Default")
      (node (ref "AH1") (pin "12") (pinfunction "4_12") (pintype "passive"))
      (node (ref "AH1") (pin "15") (pinfunction "5_15") (pintype "passive"))
      (node (ref "AH1") (pin "18") (pinfunction "6_18") (pintype "passive"))
      (node (ref "AH1") (pin "21") (pinfunction "7_21") (pintype "passive"))
      (node (ref "AH1") (pin "24") (pinfunction "8_24") (pintype "passive"))
      (node (ref "AH1") (pin "3") (pinfunction "1_3") (pintype "passive"))
      (node (ref "AH1") (pin "6") (pinfunction "2_6") (pintype "passive"))
      (node (ref "AH1") (pin "9") (pinfunction "3_9") (pintype "passive"))
      (node (ref "AH2") (pin "12") (pinfunction "4_12") (pintype "passive"))
      (node (ref "AH2") (pin "15") (pinfunction "5_15") (pintype "passive"))
      (node (ref "AH2") (pin "18") (pinfunction "6_18") (pintype "passive"))
      (node (ref "AH2") (pin "21") (pinfunction "7_21") (pintype "passive"))
      (node (ref "AH2") (pin "24") (pinfunction "8_24") (pintype "passive"))
      (node (ref "AH2") (pin "3") (pinfunction "1_3") (pintype "passive"))
      (node (ref "AH2") (pin "6") (pinfunction "2_6") (pintype "passive"))
      (node (ref "AH2") (pin "9") (pinfunction "3_9") (pintype "passive"))
      (node (ref "AH3") (pin "12") (pinfunction "4_12") (pintype "passive"))
      (node (ref "AH3") (pin "15") (pinfunction "5_15") (pintype "passive"))
      (node (ref "AH3") (pin "18") (pinfunction "6_18") (pintype "passive"))
      (node (ref "AH3") (pin "21") (pinfunction "7_21") (pintype "passive"))
      (node (ref "AH3") (pin "24") (pinfunction "8_24") (pintype "passive"))
      (node (ref "AH3") (pin "3") (pinfunction "1_3") (pintype "passive"))
      (node (ref "AH3") (pin "6") (pinfunction "2_6") (pintype "passive"))
      (node (ref "AH3") (pin "9") (pinfunction "3_9") (pintype "passive"))
      (node (ref "AH4") (pin "12") (pinfunction "4_12") (pintype "passive"))
      (node (ref "AH4") (pin "15") (pinfunction "5_15") (pintype "passive"))
      (node (ref "AH4") (pin "18") (pinfunction "6_18") (pintype "passive"))
      (node (ref "AH4") (pin "21") (pinfunction "7_21") (pintype "passive"))
      (node (ref "AH4") (pin "24") (pinfunction "8_24") (pintype "passive"))
      (node (ref "AH4") (pin "3") (pinfunction "1_3") (pintype "passive"))
      (node (ref "AH4") (pin "6") (pinfunction "2_6") (pintype "passive"))
      (node (ref "AH4") (pin "9") (pinfunction "3_9") (pintype "passive"))
      (node (ref "C10") (pin "1") (pinfunction "1_1") (pintype "passive"))
      (node (ref "C11") (pin "1") (pinfunction "1_1") (pintype "passive"))
      (node (ref "C16") (pin "1") (pinfunction "1_1") (pintype "passive"))
      (node (ref "C18") (pin "2") (pinfunction "2_2") (pintype "passive"))
      (node (ref "C19") (pin "2") (pinfunction "2_2") (pintype "passive"))
      (node (ref "C20") (pin "2") (pinfunction "2_2") (pintype "passive"))
      (node (ref "C21") (pin "1") (pinfunction "1_1") (pintype "passive"))
      (node (ref "C22") (pin "1") (pinfunction "1_1") (pintype "passive"))
      (node (ref "C3") (pin "1") (pinfunction "1_1") (pintype "passive"))
      (node (ref "C5") (pin "1") (pinfunction "1_1") (pintype "passive"))
      (node (ref "C7") (pin "1") (pinfunction "1_1") (pintype "passive"))
      (node (ref "C8") (pin "1") (pinfunction "1_1") (pintype "passive"))
      (node (ref "C9") (pin "1") (pinfunction "1_1") (pintype "passive"))
      (node (ref "CONN2") (pin "2") (pinfunction "2_2") (pintype "passive"))
      (node (ref "R10") (pin "2") (pinfunction "2_2") (pintype "passive"))
      (node (ref "R11") (pin "1") (pinfunction "1_1") (pintype "passive"))
      (node (ref "R13") (pin "1") (pinfunction "1_1") (pintype "passive"))
      (node (ref "R14") (pin "1") (pinfunction "1_1") (pintype "passive"))
      (node (ref "R15") (pin "1") (pinfunction "1_1") (pintype "passive"))
      (node (ref "R16") (pin "1") (pinfunction "1_1") (pintype "passive"))
      (node (ref "R17") (pin "1") (pinfunction "1_1") (pintype "passive"))
      (node (ref "R18") (pin "1") (pinfunction "1_1") (pintype "passive"))
      (node (ref "R9") (pin "1") (pinfunction "1_1") (pintype "passive"))
      (node (ref "U1") (pin "1") (pinfunction "VBAT_1") (pintype "bidirectional"))
      (node (ref "U1") (pin "13") (pinfunction "VDDA_13") (pintype "bidirectional"))
      (node (ref "U1") (pin "19") (pinfunction "VDD_19") (pintype "bidirectional"))
      (node (ref "U1") (pin "32") (pinfunction "VDD_32") (pintype "bidirectional"))
      (node (ref "U1") (pin "48") (pinfunction "VDD_48") (pintype "bidirectional"))
      (node (ref "U1") (pin "64") (pinfunction "VDD_64") (pintype "bidirectional"))
      (node (ref "U4") (pin "16") (pinfunction "VCC_16") (pintype "power_in"))
      (node (ref "U4") (pin "6") (pinfunction "E3_6") (pintype "input"))
      (node (ref "U5") (pin "24") (pinfunction "VCC_24") (pintype "passive"))
      (node (ref "U6") (pin "24") (pinfunction "VCC_24") (pintype "passive"))
      (node (ref "U7") (pin "16") (pinfunction "VCC_16") (pintype "power_in"))
      (node (ref "U7") (pin "6") (pinfunction "E3_6") (pintype "input"))
      (node (ref "U8") (pin "10") (pinfunction "COM_10") (pintype "passive"))
      (node (ref "VR2") (pin "3") (pinfunction "VOUT_3") (pintype "passive"))
    )
    (net (code "2") (name "+5V") (class "Default")
      (node (ref "C12") (pin "1") (pinfunction "1_1") (pintype "passive"))
      (node (ref "C14") (pin "1") (pinfunction "1_1") (pintype "passive"))
      (node (ref "C15") (pin "2") (pinfunction "2_2") (pintype "passive"))
      (node (ref "C4") (pin "2") (pinfunction "2_2") (pintype "passive"))
      (node (ref "C6") (pin "+") (pinfunction "+_+") (pintype "passive"))
      (node (ref "CONN1") (pin "VBUS") (pinfunction "VBUS_VBUS") (pintype "bidirectional"))
      (node (ref "D17") (pin "4") (pinfunction "VCC_4") (pintype "passive"))
      (node (ref "R4") (pin "1") (pinfunction "1_1") (pintype "passive"))
      (node (ref "R8") (pin "1") (pinfunction "1_1") (pintype "passive"))
      (node (ref "U2") (pin "7") (pinfunction "VE_7") (pintype "input"))
      (node (ref "U2") (pin "8") (pinfunction "VCC_8") (pintype "power_in"))
      (node (ref "VR1") (pin "1") (pinfunction "IN_1") (pintype "power_in"))
      (node (ref "VR1") (pin "3") (pinfunction "EN_3") (pintype "input"))
      (node (ref "VR2") (pin "1") (pinfunction "VIN_1") (pintype "passive"))
    )
    (net (code "3") (name "A_IN_0") (class "Default")
      (node (ref "AH1") (pin "2") (pinfunction "1_2") (pintype "passive"))
      (node (ref "U5") (pin "23") (pinfunction "Y8_23") (pintype "bidirectional"))
    )
    (net (code "4") (name "A_IN_1") (class "Default")
      (node (ref "AH1") (pin "5") (pinfunction "2_5") (pintype "passive"))
      (node (ref "U5") (pin "22") (pinfunction "Y9_22") (pintype "bidirectional"))
    )
    (net (code "5") (name "A_IN_2") (class "Default")
      (node (ref "AH1") (pin "8") (pinfunction "3_8") (pintype "passive"))
      (node (ref "U5") (pin "21") (pinfunction "Y10_21") (pintype "bidirectional"))
    )
    (net (code "6") (name "A_IN_3") (class "Default")
      (node (ref "AH1") (pin "11") (pinfunction "4_11") (pintype "passive"))
      (node (ref "U5") (pin "20") (pinfunction "Y11_20") (pintype "bidirectional"))
    )
    (net (code "7") (name "A_IN_4") (class "Default")
      (node (ref "AH1") (pin "14") (pinfunction "5_14") (pintype "passive"))
      (node (ref "U5") (pin "19") (pinfunction "Y12_19") (pintype "bidirectional"))
    )
    (net (code "8") (name "A_IN_5") (class "Default")
      (node (ref "AH1") (pin "17") (pinfunction "6_17") (pintype "passive"))
      (node (ref "U5") (pin "18") (pinfunction "Y13_18") (pintype "bidirectional"))
    )
    (net (code "9") (name "A_IN_6") (class "Default")
      (node (ref "AH1") (pin "20") (pinfunction "7_20") (pintype "passive"))
      (node (ref "U5") (pin "17") (pinfunction "Y14_17") (pintype "bidirectional"))
    )
    (net (code "10") (name "A_IN_7") (class "Default")
      (node (ref "AH1") (pin "23") (pinfunction "8_23") (pintype "passive"))
      (node (ref "U5") (pin "16") (pinfunction "Y15_16") (pintype "bidirectional"))
    )
    (net (code "11") (name "A_IN_8") (class "Default")
      (node (ref "AH2") (pin "2") (pinfunction "1_2") (pintype "passive"))
      (node (ref "U5") (pin "2") (pinfunction "Y7_2") (pintype "bidirectional"))
    )
    (net (code "12") (name "A_IN_9") (class "Default")
      (node (ref "AH2") (pin "5") (pinfunction "2_5") (pintype "passive"))
      (node (ref "U5") (pin "3") (pinfunction "Y6_3") (pintype "bidirectional"))
    )
    (net (code "13") (name "A_IN_10") (class "Default")
      (node (ref "AH2") (pin "8") (pinfunction "3_8") (pintype "passive"))
      (node (ref "U5") (pin "4") (pinfunction "Y5_4") (pintype "bidirectional"))
    )
    (net (code "14") (name "A_IN_11") (class "Default")
      (node (ref "AH2") (pin "11") (pinfunction "4_11") (pintype "passive"))
      (node (ref "U5") (pin "5") (pinfunction "Y4_5") (pintype "bidirectional"))
    )
    (net (code "15") (name "A_IN_12") (class "Default")
      (node (ref "AH2") (pin "14") (pinfunction "5_14") (pintype "passive"))
      (node (ref "U5") (pin "6") (pinfunction "Y3_6") (pintype "bidirectional"))
    )
    (net (code "16") (name "A_IN_13") (class "Default")
      (node (ref "AH2") (pin "17") (pinfunction "6_17") (pintype "passive"))
      (node (ref "U5") (pin "7") (pinfunction "Y2_7") (pintype "bidirectional"))
    )
    (net (code "17") (name "A_IN_14") (class "Default")
      (node (ref "AH2") (pin "20") (pinfunction "7_20") (pintype "passive"))
      (node (ref "U5") (pin "8") (pinfunction "Y1_8") (pintype "bidirectional"))
    )
    (net (code "18") (name "A_IN_15") (class "Default")
      (node (ref "AH2") (pin "23") (pinfunction "8_23") (pintype "passive"))
      (node (ref "U5") (pin "9") (pinfunction "Y0_9") (pintype "bidirectional"))
    )
    (net (code "19") (name "A_IN_16") (class "Default")
      (node (ref "AH3") (pin "2") (pinfunction "1_2") (pintype "passive"))
      (node (ref "U6") (pin "23") (pinfunction "Y8_23") (pintype "bidirectional"))
    )
    (net (code "20") (name "A_IN_17") (class "Default")
      (node (ref "AH3") (pin "5") (pinfunction "2_5") (pintype "passive"))
      (node (ref "U6") (pin "22") (pinfunction "Y9_22") (pintype "bidirectional"))
    )
    (net (code "21") (name "A_IN_18") (class "Default")
      (node (ref "AH3") (pin "8") (pinfunction "3_8") (pintype "passive"))
      (node (ref "U6") (pin "21") (pinfunction "Y10_21") (pintype "bidirectional"))
    )
    (net (code "22") (name "A_IN_19") (class "Default")
      (node (ref "AH3") (pin "11") (pinfunction "4_11") (pintype "passive"))
      (node (ref "U6") (pin "20") (pinfunction "Y11_20") (pintype "bidirectional"))
    )
    (net (code "23") (name "A_IN_20") (class "Default")
      (node (ref "AH3") (pin "14") (pinfunction "5_14") (pintype "passive"))
      (node (ref "U6") (pin "19") (pinfunction "Y12_19") (pintype "bidirectional"))
    )
    (net (code "24") (name "A_IN_21") (class "Default")
      (node (ref "AH3") (pin "17") (pinfunction "6_17") (pintype "passive"))
      (node (ref "U6") (pin "18") (pinfunction "Y13_18") (pintype "bidirectional"))
    )
    (net (code "25") (name "A_IN_22") (class "Default")
      (node (ref "AH3") (pin "20") (pinfunction "7_20") (pintype "passive"))
      (node (ref "U6") (pin "17") (pinfunction "Y14_17") (pintype "bidirectional"))
    )
    (net (code "26") (name "A_IN_23") (class "Default")
      (node (ref "AH3") (pin "23") (pinfunction "8_23") (pintype "passive"))
      (node (ref "U6") (pin "16") (pinfunction "Y15_16") (pintype "bidirectional"))
    )
    (net (code "27") (name "A_IN_24") (class "Default")
      (node (ref "AH4") (pin "2") (pinfunction "1_2") (pintype "passive"))
      (node (ref "U6") (pin "2") (pinfunction "Y7_2") (pintype "bidirectional"))
    )
    (net (code "28") (name "A_IN_25") (class "Default")
      (node (ref "AH4") (pin "5") (pinfunction "2_5") (pintype "passive"))
      (node (ref "U6") (pin "3") (pinfunction "Y6_3") (pintype "bidirectional"))
    )
    (net (code "29") (name "A_IN_26") (class "Default")
      (node (ref "AH4") (pin "8") (pinfunction "3_8") (pintype "passive"))
      (node (ref "U6") (pin "4") (pinfunction "Y5_4") (pintype "bidirectional"))
    )
    (net (code "30") (name "A_IN_27") (class "Default")
      (node (ref "AH4") (pin "11") (pinfunction "4_11") (pintype "passive"))
      (node (ref "U6") (pin "5") (pinfunction "Y4_5") (pintype "bidirectional"))
    )
    (net (code "31") (name "A_IN_28") (class "Default")
      (node (ref "AH4") (pin "14") (pinfunction "5_14") (pintype "passive"))
      (node (ref "U6") (pin "6") (pinfunction "Y3_6") (pintype "bidirectional"))
    )
    (net (code "32") (name "A_IN_29") (class "Default")
      (node (ref "AH4") (pin "17") (pinfunction "6_17") (pintype "passive"))
      (node (ref "U6") (pin "7") (pinfunction "Y2_7") (pintype "bidirectional"))
    )
    (net (code "33") (name "A_IN_30") (class "Default")
      (node (ref "AH4") (pin "20") (pinfunction "7_20") (pintype "passive"))
      (node (ref "U6") (pin "8") (pinfunction "Y1_8") (pintype "bidirectional"))
    )
    (net (code "34") (name "A_IN_31") (class "Default")
      (node (ref "AH4") (pin "23") (pinfunction "8_23") (pintype "passive"))
      (node (ref "U6") (pin "9") (pinfunction "Y0_9") (pintype "bidirectional"))
    )
    (net (code "35") (name "BC_1") (class "Default")
      (node (ref "IH1") (pin "1") (pinfunction "1_1") (pintype "passive"))
      (node (ref "IH1") (pin "13") (pinfunction "13_13") (pintype "passive"))
      (node (ref "IH1") (pin "5") (pinfunction "5_5") (pintype "passive"))
      (node (ref "IH1") (pin "9") (pinfunction "9_9") (pintype "passive"))
      (node (ref "IH5") (pin "1") (pinfunction "1_1") (pintype "passive"))
      (node (ref "IH5") (pin "13") (pinfunction "13_13") (pintype "passive"))
      (node (ref "IH5") (pin "5") (pinfunction "5_5") (pintype "passive"))
      (node (ref "IH5") (pin "9") (pinfunction "9_9") (pintype "passive"))
      (node (ref "U4") (pin "15") (pinfunction "~{Y0}_15") (pintype "output"))
    )
    (net (code "36") (name "BC_2") (class "Default")
      (node (ref "IH1") (pin "11") (pinfunction "11_11") (pintype "passive"))
      (node (ref "IH1") (pin "15") (pinfunction "15_15") (pintype "passive"))
      (node (ref "IH1") (pin "3") (pinfunction "3_3") (pintype "passive"))
      (node (ref "IH1") (pin "7") (pinfunction "7_7") (pintype "passive"))
      (node (ref "IH5") (pin "11") (pinfunction "11_11") (pintype "passive"))
      (node (ref "IH5") (pin "15") (pinfunction "15_15") (pintype "passive"))
      (node (ref "IH5") (pin "3") (pinfunction "3_3") (pintype "passive"))
      (node (ref "IH5") (pin "7") (pinfunction "7_7") (pintype "passive"))
      (node (ref "U4") (pin "7") (pinfunction "~{Y7}_7") (pintype "output"))
    )
    (net (code "37") (name "BC_3") (class "Default")
      (node (ref "IH2") (pin "1") (pinfunction "1_1") (pintype "passive"))
      (node (ref "IH2") (pin "13") (pinfunction "13_13") (pintype "passive"))
      (node (ref "IH2") (pin "5") (pinfunction "5_5") (pintype "passive"))
      (node (ref "IH2") (pin "9") (pinfunction "9_9") (pintype "passive"))
      (node (ref "IH6") (pin "1") (pinfunction "1_1") (pintype "passive"))
      (node (ref "IH6") (pin "13") (pinfunction "13_13") (pintype "passive"))
      (node (ref "IH6") (pin "5") (pinfunction "5_5") (pintype "passive"))
      (node (ref "IH6") (pin "9") (pinfunction "9_9") (pintype "passive"))
      (node (ref "U4") (pin "13") (pinfunction "~{Y2}_13") (pintype "output"))
    )
    (net (code "38") (name "BC_4") (class "Default")
      (node (ref "IH2") (pin "11") (pinfunction "11_11") (pintype "passive"))
      (node (ref "IH2") (pin "15") (pinfunction "15_15") (pintype "passive"))
      (node (ref "IH2") (pin "3") (pinfunction "3_3") (pintype "passive"))
      (node (ref "IH2") (pin "7") (pinfunction "7_7") (pintype "passive"))
      (node (ref "IH6") (pin "11") (pinfunction "11_11") (pintype "passive"))
      (node (ref "IH6") (pin "15") (pinfunction "15_15") (pintype "passive"))
      (node (ref "IH6") (pin "3") (pinfunction "3_3") (pintype "passive"))
      (node (ref "IH6") (pin "7") (pinfunction "7_7") (pintype "passive"))
      (node (ref "U4") (pin "14") (pinfunction "~{Y1}_14") (pintype "output"))
    )
    (net (code "39") (name "BC_5") (class "Default")
      (node (ref "IH3") (pin "1") (pinfunction "1_1") (pintype "passive"))
      (node (ref "IH3") (pin "13") (pinfunction "13_13") (pintype "passive"))
      (node (ref "IH3") (pin "5") (pinfunction "5_5") (pintype "passive"))
      (node (ref "IH3") (pin "9") (pinfunction "9_9") (pintype "passive"))
      (node (ref "IH7") (pin "1") (pinfunction "1_1") (pintype "passive"))
      (node (ref "IH7") (pin "13") (pinfunction "13_13") (pintype "passive"))
      (node (ref "IH7") (pin "5") (pinfunction "5_5") (pintype "passive"))
      (node (ref "IH7") (pin "9") (pinfunction "9_9") (pintype "passive"))
      (node (ref "U4") (pin "11") (pinfunction "~{Y4}_11") (pintype "output"))
    )
    (net (code "40") (name "BC_6") (class "Default")
      (node (ref "IH3") (pin "11") (pinfunction "11_11") (pintype "passive"))
      (node (ref "IH3") (pin "15") (pinfunction "15_15") (pintype "passive"))
      (node (ref "IH3") (pin "3") (pinfunction "3_3") (pintype "passive"))
      (node (ref "IH3") (pin "7") (pinfunction "7_7") (pintype "passive"))
      (node (ref "IH7") (pin "11") (pinfunction "11_11") (pintype "passive"))
      (node (ref "IH7") (pin "15") (pinfunction "15_15") (pintype "passive"))
      (node (ref "IH7") (pin "3") (pinfunction "3_3") (pintype "passive"))
      (node (ref "IH7") (pin "7") (pinfunction "7_7") (pintype "passive"))
      (node (ref "U4") (pin "12") (pinfunction "~{Y3}_12") (pintype "output"))
    )
    (net (code "41") (name "BC_7") (class "Default")
      (node (ref "IH4") (pin "1") (pinfunction "1_1") (pintype "passive"))
      (node (ref "IH4") (pin "13") (pinfunction "13_13") (pintype "passive"))
      (node (ref "IH4") (pin "5") (pinfunction "5_5") (pintype "passive"))
      (node (ref "IH4") (pin "9") (pinfunction "9_9") (pintype "passive"))
      (node (ref "IH8") (pin "1") (pinfunction "1_1") (pintype "passive"))
      (node (ref "IH8") (pin "13") (pinfunction "13_13") (pintype "passive"))
      (node (ref "IH8") (pin "5") (pinfunction "5_5") (pintype "passive"))
      (node (ref "IH8") (pin "9") (pinfunction "9_9") (pintype "passive"))
      (node (ref "U4") (pin "10") (pinfunction "~{Y5}_10") (pintype "output"))
    )
    (net (code "42") (name "BC_8") (class "Default")
      (node (ref "IH4") (pin "11") (pinfunction "11_11") (pintype "passive"))
      (node (ref "IH4") (pin "15") (pinfunction "15_15") (pintype "passive"))
      (node (ref "IH4") (pin "3") (pinfunction "3_3") (pintype "passive"))
      (node (ref "IH4") (pin "7") (pinfunction "7_7") (pintype "passive"))
      (node (ref "IH8") (pin "11") (pinfunction "11_11") (pintype "passive"))
      (node (ref "IH8") (pin "15") (pinfunction "15_15") (pintype "passive"))
      (node (ref "IH8") (pin "3") (pinfunction "3_3") (pintype "passive"))
      (node (ref "IH8") (pin "7") (pinfunction "7_7") (pintype "passive"))
      (node (ref "U4") (pin "9") (pinfunction "~{Y6}_9") (pintype "output"))
    )
    (net (code "43") (name "BOOT0") (class "Default")
      (node (ref "R3") (pin "2") (pinfunction "2_2") (pintype "passive"))
      (node (ref "U1") (pin "60") (pinfunction "BOOT0_60") (pintype "bidirectional"))
    )
    (net (code "44") (name "BR_1") (class "Default")
      (node (ref "D1") (pin "3") (pinfunction "3_3") (pintype "passive"))
      (node (ref "D2") (pin "3") (pinfunction "3_3") (pintype "passive"))
      (node (ref "D3") (pin "3") (pinfunction "3_3") (pintype "passive"))
      (node (ref "D4") (pin "3") (pinfunction "3_3") (pintype "passive"))
      (node (ref "R9") (pin "2") (pinfunction "2_2") (pintype "passive"))
      (node (ref "U1") (pin "20") (pinfunction "PA4_20") (pintype "bidirectional"))
    )
    (net (code "45") (name "BR_2") (class "Default")
      (node (ref "D5") (pin "3") (pinfunction "3_3") (pintype "passive"))
      (node (ref "D6") (pin "3") (pinfunction "3_3") (pintype "passive"))
      (node (ref "D7") (pin "3") (pinfunction "3_3") (pintype "passive"))
      (node (ref "D8") (pin "3") (pinfunction "3_3") (pintype "passive"))
      (node (ref "R11") (pin "2") (pinfunction "2_2") (pintype "passive"))
      (node (ref "U1") (pin "21") (pinfunction "PA5_21") (pintype "bidirectional"))
    )
    (net (code "46") (name "BR_3") (class "Default")
      (node (ref "D10") (pin "3") (pinfunction "3_3") (pintype "passive"))
      (node (ref "D11") (pin "3") (pinfunction "3_3") (pintype "passive"))
      (node (ref "D12") (pin "3") (pinfunction "3_3") (pintype "passive"))
      (node (ref "D9") (pin "3") (pinfunction "3_3") (pintype "passive"))
      (node (ref "R13") (pin "2") (pinfunction "2_2") (pintype "passive"))
      (node (ref "U1") (pin "24") (pinfunction "PC4_24") (pintype "bidirectional"))
    )
    (net (code "47") (name "BR_4") (class "Default")
      (node (ref "D13") (pin "3") (pinfunction "3_3") (pintype "passive"))
      (node (ref "D14") (pin "3") (pinfunction "3_3") (pintype "passive"))
      (node (ref "D15") (pin "3") (pinfunction "3_3") (pintype "passive"))
      (node (ref "D16") (pin "3") (pinfunction "3_3") (pintype "passive"))
      (node (ref "R14") (pin "2") (pinfunction "2_2") (pintype "passive"))
      (node (ref "U1") (pin "25") (pinfunction "PC5_25") (pintype "bidirectional"))
    )
    (net (code "48") (name "BR_5") (class "Default")
      (node (ref "D30") (pin "3") (pinfunction "3_3") (pintype "passive"))
      (node (ref "D31") (pin "3") (pinfunction "3_3") (pintype "passive"))
      (node (ref "D32") (pin "3") (pinfunction "3_3") (pintype "passive"))
      (node (ref "D33") (pin "3") (pinfunction "3_3") (pintype "passive"))
      (node (ref "R15") (pin "2") (pinfunction "2_2") (pintype "passive"))
      (node (ref "U1") (pin "30") (pinfunction "PB11_30") (pintype "bidirectional"))
    )
    (net (code "49") (name "BR_6") (class "Default")
      (node (ref "D26") (pin "3") (pinfunction "3_3") (pintype "passive"))
      (node (ref "D27") (pin "3") (pinfunction "3_3") (pintype "passive"))
      (node (ref "D28") (pin "3") (pinfunction "3_3") (pintype "passive"))
      (node (ref "D29") (pin "3") (pinfunction "3_3") (pintype "passive"))
      (node (ref "R16") (pin "2") (pinfunction "2_2") (pintype "passive"))
      (node (ref "U1") (pin "29") (pinfunction "PB10_29") (pintype "bidirectional"))
    )
    (net (code "50") (name "BR_7") (class "Default")
      (node (ref "D22") (pin "3") (pinfunction "3_3") (pintype "passive"))
      (node (ref "D23") (pin "3") (pinfunction "3_3") (pintype "passive"))
      (node (ref "D24") (pin "3") (pinfunction "3_3") (pintype "passive"))
      (node (ref "D25") (pin "3") (pinfunction "3_3") (pintype "passive"))
      (node (ref "R17") (pin "2") (pinfunction "2_2") (pintype "passive"))
      (node (ref "U1") (pin "28") (pinfunction "PB2_28") (pintype "bidirectional"))
    )
    (net (code "51") (name "BR_8") (class "Default")
      (node (ref "D18") (pin "3") (pinfunction "3_3") (pintype "passive"))
      (node (ref "D19") (pin "3") (pinfunction "3_3") (pintype "passive"))
      (node (ref "D20") (pin "3") (pinfunction "3_3") (pintype "passive"))
      (node (ref "D21") (pin "3") (pinfunction "3_3") (pintype "passive"))
      (node (ref "R18") (pin "2") (pinfunction "2_2") (pintype "passive"))
      (node (ref "U1") (pin "27") (pinfunction "PB1_27") (pintype "bidirectional"))
    )
    (net (code "52") (name "BTLDR_BUTTON") (class "Default")
      (node (ref "CONN2") (pin "1") (pinfunction "1_1") (pintype "passive"))
      (node (ref "U1") (pin "56") (pinfunction "PB4_56") (pintype "bidirectional"))
    )
    (net (code "53") (name "D+") (class "Default")
      (node (ref "R1") (pin "2") (pinfunction "2_2") (pintype "passive"))
      (node (ref "U1") (pin "45") (pinfunction "PA12_45") (pintype "bidirectional"))
    )
    (net (code "54") (name "D+X") (class "Default")
      (node (ref "CONN1") (pin "D+") (pinfunction "D+_D+") (pintype "bidirectional"))
      (node (ref "D17") (pin "3") (pinfunction "I/O2_3") (pintype "passive"))
      (node (ref "R1") (pin "1") (pinfunction "1_1") (pintype "passive"))
    )
    (net (code "55") (name "D-") (class "Default")
      (node (ref "R2") (pin "1") (pinfunction "1_1") (pintype "passive"))
      (node (ref "U1") (pin "44") (pinfunction "PA11_44") (pintype "bidirectional"))
    )
    (net (code "56") (name "D-X") (class "Default")
      (node (ref "CONN1") (pin "D-") (pinfunction "D-_D-") (pintype "bidirectional"))
      (node (ref "D17") (pin "2") (pinfunction "I/O1_2") (pintype "passive"))
      (node (ref "R2") (pin "2") (pinfunction "2_2") (pintype "passive"))
    )
    (net (code "57") (name "DEC_DI_A0") (class "Default")
      (node (ref "U1") (pin "39") (pinfunction "PC8_39") (pintype "bidirectional"))
      (node (ref "U4") (pin "1") (pinfunction "A0_1") (pintype "input"))
    )
    (net (code "58") (name "DEC_DI_A1") (class "Default")
      (node (ref "U1") (pin "40") (pinfunction "PC9_40") (pintype "bidirectional"))
      (node (ref "U4") (pin "2") (pinfunction "A1_2") (pintype "input"))
    )
    (net (code "59") (name "DEC_DI_A2") (class "Default")
      (node (ref "U1") (pin "41") (pinfunction "PA8_41") (pintype "bidirectional"))
      (node (ref "U4") (pin "3") (pinfunction "A2_3") (pintype "input"))
    )
    (net (code "60") (name "DEC_DO_A0") (class "Default")
      (node (ref "U1") (pin "16") (pinfunction "PA2_16") (pintype "bidirectional"))
      (node (ref "U7") (pin "1") (pinfunction "A0_1") (pintype "input"))
    )
    (net (code "61") (name "DEC_DO_A1") (class "Default")
      (node (ref "U1") (pin "15") (pinfunction "PA1_15") (pintype "bidirectional"))
      (node (ref "U7") (pin "2") (pinfunction "A1_2") (pintype "input"))
    )
    (net (code "62") (name "DEC_DO_A2") (class "Default")
      (node (ref "U1") (pin "14") (pinfunction "PA0_14") (pintype "bidirectional"))
      (node (ref "U7") (pin "3") (pinfunction "A2_3") (pintype "input"))
    )
    (net (code "63") (name "GND") (class "Default")
      (node (ref "AH1") (pin "1") (pinfunction "1_1") (pintype "passive"))
      (node (ref "AH1") (pin "10") (pinfunction "4_10") (pintype "passive"))
      (node (ref "AH1") (pin "13") (pinfunction "5_13") (pintype "passive"))
      (node (ref "AH1") (pin "16") (pinfunction "6_16") (pintype "passive"))
      (node (ref "AH1") (pin "19") (pinfunction "7_19") (pintype "passive"))
      (node (ref "AH1") (pin "22") (pinfunction "8_22") (pintype "passive"))
      (node (ref "AH1") (pin "4") (pinfunction "2_4") (pintype "passive"))
      (node (ref "AH1") (pin "7") (pinfunction "3_7") (pintype "passive"))
      (node (ref "AH2") (pin "1") (pinfunction "1_1") (pintype "passive"))
      (node (ref "AH2") (pin "10") (pinfunction "4_10") (pintype "passive"))
      (node (ref "AH2") (pin "13") (pinfunction "5_13") (pintype "passive"))
      (node (ref "AH2") (pin "16") (pinfunction "6_16") (pintype "passive"))
      (node (ref "AH2") (pin "19") (pinfunction "7_19") (pintype "passive"))
      (node (ref "AH2") (pin "22") (pinfunction "8_22") (pintype "passive"))
      (node (ref "AH2") (pin "4") (pinfunction "2_4") (pintype "passive"))
      (node (ref "AH2") (pin "7") (pinfunction "3_7") (pintype "passive"))
      (node (ref "AH3") (pin "1") (pinfunction "1_1") (pintype "passive"))
      (node (ref "AH3") (pin "10") (pinfunction "4_10") (pintype "passive"))
      (node (ref "AH3") (pin "13") (pinfunction "5_13") (pintype "passive"))
      (node (ref "AH3") (pin "16") (pinfunction "6_16") (pintype "passive"))
      (node (ref "AH3") (pin "19") (pinfunction "7_19") (pintype "passive"))
      (node (ref "AH3") (pin "22") (pinfunction "8_22") (pintype "passive"))
      (node (ref "AH3") (pin "4") (pinfunction "2_4") (pintype "passive"))
      (node (ref "AH3") (pin "7") (pinfunction "3_7") (pintype "passive"))
      (node (ref "AH4") (pin "1") (pinfunction "1_1") (pintype "passive"))
      (node (ref "AH4") (pin "10") (pinfunction "4_10") (pintype "passive"))
      (node (ref "AH4") (pin "13") (pinfunction "5_13") (pintype "passive"))
      (node (ref "AH4") (pin "16") (pinfunction "6_16") (pintype "passive"))
      (node (ref "AH4") (pin "19") (pinfunction "7_19") (pintype "passive"))
      (node (ref "AH4") (pin "22") (pinfunction "8_22") (pintype "passive"))
      (node (ref "AH4") (pin "4") (pinfunction "2_4") (pintype "passive"))
      (node (ref "AH4") (pin "7") (pinfunction "3_7") (pintype "passive"))
      (node (ref "C1") (pin "1") (pinfunction "1_1") (pintype "passive"))
      (node (ref "C10") (pin "2") (pinfunction "2_2") (pintype "passive"))
      (node (ref "C11") (pin "2") (pinfunction "2_2") (pintype "passive"))
      (node (ref "C12") (pin "2") (pinfunction "2_2") (pintype "passive"))
      (node (ref "C13") (pin "2") (pinfunction "2_2") (pintype "passive"))
      (node (ref "C14") (pin "2") (pinfunction "2_2") (pintype "passive"))
      (node (ref "C15") (pin "1") (pinfunction "1_1") (pintype "passive"))
      (node (ref "C16") (pin "2") (pinfunction "2_2") (pintype "passive"))
      (node (ref "C17") (pin "2") (pinfunction "2_2") (pintype "passive"))
      (node (ref "C18") (pin "1") (pinfunction "1_1") (pintype "passive"))
      (node (ref "C19") (pin "1") (pinfunction "1_1") (pintype "passive"))
      (node (ref "C2") (pin "2") (pinfunction "2_2") (pintype "passive"))
      (node (ref "C20") (pin "1") (pinfunction "1_1") (pintype "passive"))
      (node (ref "C21") (pin "2") (pinfunction "2_2") (pintype "passive"))
      (node (ref "C22") (pin "2") (pinfunction "2_2") (pintype "passive"))
      (node (ref "C23") (pin "2") (pinfunction "2_2") (pintype "passive"))
      (node (ref "C24") (pin "2") (pinfunction "2_2") (pintype "passive"))
      (node (ref "C3") (pin "2") (pinfunction "2_2") (pintype "passive"))
      (node (ref "C4") (pin "1") (pinfunction "1_1") (pintype "passive"))
      (node (ref "C5") (pin "2") (pinfunction "2_2") (pintype "passive"))
      (node (ref "C6") (pin "-") (pinfunction "-_-") (pintype "passive"))
      (node (ref "C7") (pin "2") (pinfunction "2_2") (pintype "passive"))
      (node (ref "C8") (pin "2") (pinfunction "2_2") (pintype "passive"))
      (node (ref "C9") (pin "2") (pinfunction "2_2") (pintype "passive"))
      (node (ref "CONN1") (pin "GND") (pinfunction "GND_GND") (pintype "bidirectional"))
      (node (ref "CONN4") (pin "2") (pinfunction "2_2") (pintype "passive"))
      (node (ref "CONN5") (pin "4") (pinfunction "4_4") (pintype "passive"))
      (node (ref "CONN6") (pin "3") (pinfunction "3_3") (pintype "passive"))
      (node (ref "CONN7") (pin "3") (pinfunction "3_3") (pintype "passive"))
      (node (ref "D17") (pin "1") (pinfunction "GND_1") (pintype "passive"))
      (node (ref "D35") (pin "C") (pinfunction "C_C") (pintype "passive"))
      (node (ref "D36") (pin "C") (pinfunction "C_C") (pintype "passive"))
      (node (ref "D37") (pin "C") (pinfunction "C_C") (pintype "passive"))
      (node (ref "L1") (pin "1") (pinfunction "1_1") (pintype "passive"))
      (node (ref "R3") (pin "1") (pinfunction "1_1") (pintype "passive"))
      (node (ref "U1") (pin "12") (pinfunction "VSSA_12") (pintype "bidirectional"))
      (node (ref "U1") (pin "18") (pinfunction "VSS_18") (pintype "bidirectional"))
      (node (ref "U1") (pin "63") (pinfunction "VSS_63") (pintype "bidirectional"))
      (node (ref "U2") (pin "5") (pinfunction "GND_5") (pintype "power_in"))
      (node (ref "U4") (pin "4") (pinfunction "~{E1}_4") (pintype "input"))
      (node (ref "U4") (pin "5") (pinfunction "~{E2}_5") (pintype "input"))
      (node (ref "U4") (pin "8") (pinfunction "GND_8") (pintype "power_in"))
      (node (ref "U5") (pin "12") (pinfunction "GND_12") (pintype "passive"))
      (node (ref "U5") (pin "15") (pinfunction "~{E}_15") (pintype "input"))
      (node (ref "U6") (pin "12") (pinfunction "GND_12") (pintype "passive"))
      (node (ref "U6") (pin "15") (pinfunction "~{E}_15") (pintype "input"))
      (node (ref "U7") (pin "4") (pinfunction "~{E1}_4") (pintype "input"))
      (node (ref "U7") (pin "5") (pinfunction "~{E2}_5") (pintype "input"))
      (node (ref "U7") (pin "8") (pinfunction "GND_8") (pintype "power_in"))
      (node (ref "U8") (pin "9") (pinfunction "GND_9") (pintype "power_in"))
      (node (ref "VR1") (pin "2") (pinfunction "GND_2") (pintype "power_in"))
      (node (ref "VR2") (pin "2") (pinfunction "GND_2") (pintype "passive"))
      (node (ref "VR2") (pin "4") (pinfunction "GND_4") (pintype "passive"))
      (node (ref "Y1") (pin "2") (pinfunction "VEE_2") (pintype "passive"))
      (node (ref "Y1") (pin "4") (pinfunction "VEE_4") (pintype "passive"))
    )
    (net (code "64") (name "LC_1") (class "Default")
      (node (ref "OH1") (pin "10") (pinfunction "10_10") (pintype "passive"))
      (node (ref "OH1") (pin "12") (pinfunction "12_12") (pintype "passive"))
      (node (ref "OH1") (pin "2") (pinfunction "2_2") (pintype "passive"))
      (node (ref "OH1") (pin "4") (pinfunction "4_4") (pintype "passive"))
      (node (ref "OH1") (pin "6") (pinfunction "6_6") (pintype "passive"))
      (node (ref "OH1") (pin "8") (pinfunction "8_8") (pintype "passive"))
      (node (ref "U8") (pin "18") (pinfunction "1C_18") (pintype "open_collector"))
    )
    (net (code "65") (name "LC_2") (class "Default")
      (node (ref "OH2") (pin "10") (pinfunction "10_10") (pintype "passive"))
      (node (ref "OH2") (pin "12") (pinfunction "12_12") (pintype "passive"))
      (node (ref "OH2") (pin "2") (pinfunction "2_2") (pintype "passive"))
      (node (ref "OH2") (pin "4") (pinfunction "4_4") (pintype "passive"))
      (node (ref "OH2") (pin "6") (pinfunction "6_6") (pintype "passive"))
      (node (ref "OH2") (pin "8") (pinfunction "8_8") (pintype "passive"))
      (node (ref "U8") (pin "17") (pinfunction "2C_17") (pintype "open_collector"))
    )
    (net (code "66") (name "LC_3") (class "Default")
      (node (ref "OH3") (pin "10") (pinfunction "10_10") (pintype "passive"))
      (node (ref "OH3") (pin "12") (pinfunction "12_12") (pintype "passive"))
      (node (ref "OH3") (pin "2") (pinfunction "2_2") (pintype "passive"))
      (node (ref "OH3") (pin "4") (pinfunction "4_4") (pintype "passive"))
      (node (ref "OH3") (pin "6") (pinfunction "6_6") (pintype "passive"))
      (node (ref "OH3") (pin "8") (pinfunction "8_8") (pintype "passive"))
      (node (ref "U8") (pin "16") (pinfunction "3C_16") (pintype "open_collector"))
    )
    (net (code "67") (name "LC_4") (class "Default")
      (node (ref "OH4") (pin "10") (pinfunction "10_10") (pintype "passive"))
      (node (ref "OH4") (pin "12") (pinfunction "12_12") (pintype "passive"))
      (node (ref "OH4") (pin "2") (pinfunction "2_2") (pintype "passive"))
      (node (ref "OH4") (pin "4") (pinfunction "4_4") (pintype "passive"))
      (node (ref "OH4") (pin "6") (pinfunction "6_6") (pintype "passive"))
      (node (ref "OH4") (pin "8") (pinfunction "8_8") (pintype "passive"))
      (node (ref "U8") (pin "15") (pinfunction "4C_15") (pintype "open_collector"))
    )
    (net (code "68") (name "LC_5") (class "Default")
      (node (ref "OH5") (pin "10") (pinfunction "10_10") (pintype "passive"))
      (node (ref "OH5") (pin "12") (pinfunction "12_12") (pintype "passive"))
      (node (ref "OH5") (pin "2") (pinfunction "2_2") (pintype "passive"))
      (node (ref "OH5") (pin "4") (pinfunction "4_4") (pintype "passive"))
      (node (ref "OH5") (pin "6") (pinfunction "6_6") (pintype "passive"))
      (node (ref "OH5") (pin "8") (pinfunction "8_8") (pintype "passive"))
      (node (ref "U8") (pin "14") (pinfunction "5C_14") (pintype "open_collector"))
    )
    (net (code "69") (name "LC_6") (class "Default")
      (node (ref "OH6") (pin "10") (pinfunction "10_10") (pintype "passive"))
      (node (ref "OH6") (pin "12") (pinfunction "12_12") (pintype "passive"))
      (node (ref "OH6") (pin "2") (pinfunction "2_2") (pintype "passive"))
      (node (ref "OH6") (pin "4") (pinfunction "4_4") (pintype "passive"))
      (node (ref "OH6") (pin "6") (pinfunction "6_6") (pintype "passive"))
      (node (ref "OH6") (pin "8") (pinfunction "8_8") (pintype "passive"))
      (node (ref "U8") (pin "13") (pinfunction "6C_13") (pintype "open_collector"))
    )
    (net (code "70") (name "LC_7") (class "Default")
      (node (ref "OH7") (pin "10") (pinfunction "10_10") (pintype "passive"))
      (node (ref "OH7") (pin "12") (pinfunction "12_12") (pintype "passive"))
      (node (ref "OH7") (pin "2") (pinfunction "2_2") (pintype "passive"))
      (node (ref "OH7") (pin "4") (pinfunction "4_4") (pintype "passive"))
      (node (ref "OH7") (pin "6") (pinfunction "6_6") (pintype "passive"))
      (node (ref "OH7") (pin "8") (pinfunction "8_8") (pintype "passive"))
      (node (ref "U8") (pin "12") (pinfunction "7C_12") (pintype "open_collector"))
    )
    (net (code "71") (name "LC_8") (class "Default")
      (node (ref "OH8") (pin "10") (pinfunction "10_10") (pintype "passive"))
      (node (ref "OH8") (pin "12") (pinfunction "12_12") (pintype "passive"))
      (node (ref "OH8") (pin "2") (pinfunction "2_2") (pintype "passive"))
      (node (ref "OH8") (pin "4") (pinfunction "4_4") (pintype "passive"))
      (node (ref "OH8") (pin "6") (pinfunction "6_6") (pintype "passive"))
      (node (ref "OH8") (pin "8") (pinfunction "8_8") (pintype "passive"))
      (node (ref "U8") (pin "11") (pinfunction "8C_11") (pintype "open_collector"))
    )
    (net (code "72") (name "LEDS_VCC") (class "Default")
      (node (ref "C13") (pin "1") (pinfunction "1_1") (pintype "passive"))
      (node (ref "Q1") (pin "2") (pinfunction "S2_2") (pintype "bidirectional"))
      (node (ref "Q1") (pin "5") (pinfunction "S1_5") (pintype "bidirectional"))
      (node (ref "Q2") (pin "2") (pinfunction "S2_2") (pintype "bidirectional"))
      (node (ref "Q2") (pin "5") (pinfunction "S1_5") (pintype "bidirectional"))
      (node (ref "Q3") (pin "2") (pinfunction "S2_2") (pintype "bidirectional"))
      (node (ref "Q3") (pin "5") (pinfunction "S1_5") (pintype "bidirectional"))
      (node (ref "R19") (pin "1") (pinfunction "1_1") (pintype "passive"))
      (node (ref "R21") (pin "1") (pinfunction "1_1") (pintype "passive"))
      (node (ref "R23") (pin "1") (pinfunction "1_1") (pintype "passive"))
      (node (ref "R25") (pin "1") (pinfunction "1_1") (pintype "passive"))
      (node (ref "R27") (pin "1") (pinfunction "1_1") (pintype "passive"))
      (node (ref "R29") (pin "1") (pinfunction "1_1") (pintype "passive"))
      (node (ref "VR1") (pin "5") (pinfunction "OUT_5") (pintype "power_in"))
    )
    (net (code "73") (name "LR_1_MI") (class "Default")
      (node (ref "Q1") (pin "1") (pinfunction "G1_1") (pintype "bidirectional"))
      (node (ref "R19") (pin "2") (pinfunction "2_2") (pintype "passive"))
      (node (ref "U1") (pin "62") (pinfunction "PB9_62") (pintype "bidirectional"))
    )
    (net (code "74") (name "LR_1_MO") (class "Default")
      (node (ref "OH1") (pin "1") (pinfunction "1_1") (pintype "passive"))
      (node (ref "OH2") (pin "1") (pinfunction "1_1") (pintype "passive"))
      (node (ref "OH3") (pin "1") (pinfunction "1_1") (pintype "passive"))
      (node (ref "OH4") (pin "1") (pinfunction "1_1") (pintype "passive"))
      (node (ref "OH5") (pin "1") (pinfunction "1_1") (pintype "passive"))
      (node (ref "OH6") (pin "1") (pinfunction "1_1") (pintype "passive"))
      (node (ref "OH7") (pin "1") (pinfunction "1_1") (pintype "passive"))
      (node (ref "OH8") (pin "1") (pinfunction "1_1") (pintype "passive"))
      (node (ref "R20") (pin "1") (pinfunction "1_1") (pintype "passive"))
    )
    (net (code "75") (name "LR_2_MI") (class "Default")
      (node (ref "Q1") (pin "3") (pinfunction "G2_3") (pintype "bidirectional"))
      (node (ref "R21") (pin "2") (pinfunction "2_2") (pintype "passive"))
      (node (ref "U1") (pin "61") (pinfunction "PB8_61") (pintype "bidirectional"))
    )
    (net (code "76") (name "LR_2_MO") (class "Default")
      (node (ref "OH1") (pin "3") (pinfunction "3_3") (pintype "passive"))
      (node (ref "OH2") (pin "3") (pinfunction "3_3") (pintype "passive"))
      (node (ref "OH3") (pin "3") (pinfunction "3_3") (pintype "passive"))
      (node (ref "OH4") (pin "3") (pinfunction "3_3") (pintype "passive"))
      (node (ref "OH5") (pin "3") (pinfunction "3_3") (pintype "passive"))
      (node (ref "OH6") (pin "3") (pinfunction "3_3") (pintype "passive"))
      (node (ref "OH7") (pin "3") (pinfunction "3_3") (pintype "passive"))
      (node (ref "OH8") (pin "3") (pinfunction "3_3") (pintype "passive"))
      (node (ref "R22") (pin "2") (pinfunction "2_2") (pintype "passive"))
    )
    (net (code "77") (name "LR_3_MI") (class "Default")
      (node (ref "Q2") (pin "1") (pinfunction "G1_1") (pintype "bidirectional"))
      (node (ref "R27") (pin "2") (pinfunction "2_2") (pintype "passive"))
      (node (ref "U1") (pin "17") (pinfunction "PA3_17") (pintype "bidirectional"))
    )
    (net (code "78") (name "LR_3_MO") (class "Default")
      (node (ref "OH1") (pin "9") (pinfunction "9_9") (pintype "passive"))
      (node (ref "OH2") (pin "9") (pinfunction "9_9") (pintype "passive"))
      (node (ref "OH3") (pin "9") (pinfunction "9_9") (pintype "passive"))
      (node (ref "OH4") (pin "9") (pinfunction "9_9") (pintype "passive"))
      (node (ref "OH5") (pin "9") (pinfunction "9_9") (pintype "passive"))
      (node (ref "OH6") (pin "9") (pinfunction "9_9") (pintype "passive"))
      (node (ref "OH7") (pin "9") (pinfunction "9_9") (pintype "passive"))
      (node (ref "OH8") (pin "9") (pinfunction "9_9") (pintype "passive"))
      (node (ref "R28") (pin "1") (pinfunction "1_1") (pintype "passive"))
    )
    (net (code "79") (name "LR_4_MI") (class "Default")
      (node (ref "Q2") (pin "3") (pinfunction "G2_3") (pintype "bidirectional"))
      (node (ref "R29") (pin "2") (pinfunction "2_2") (pintype "passive"))
      (node (ref "U1") (pin "22") (pinfunction "PA6_22") (pintype "bidirectional"))
    )
    (net (code "80") (name "LR_4_MO") (class "Default")
      (node (ref "OH1") (pin "11") (pinfunction "11_11") (pintype "passive"))
      (node (ref "OH2") (pin "11") (pinfunction "11_11") (pintype "passive"))
      (node (ref "OH3") (pin "11") (pinfunction "11_11") (pintype "passive"))
      (node (ref "OH4") (pin "11") (pinfunction "11_11") (pintype "passive"))
      (node (ref "OH5") (pin "11") (pinfunction "11_11") (pintype "passive"))
      (node (ref "OH6") (pin "11") (pinfunction "11_11") (pintype "passive"))
      (node (ref "OH7") (pin "11") (pinfunction "11_11") (pintype "passive"))
      (node (ref "OH8") (pin "11") (pinfunction "11_11") (pintype "passive"))
      (node (ref "R30") (pin "1") (pinfunction "1_1") (pintype "passive"))
    )
    (net (code "81") (name "LR_5_MI") (class "Default")
      (node (ref "Q3") (pin "1") (pinfunction "G1_1") (pintype "bidirectional"))
      (node (ref "R23") (pin "2") (pinfunction "2_2") (pintype "passive"))
      (node (ref "U1") (pin "23") (pinfunction "PA7_23") (pintype "bidirectional"))
    )
    (net (code "82") (name "LR_5_MO") (class "Default")
      (node (ref "OH1") (pin "5") (pinfunction "5_5") (pintype "passive"))
      (node (ref "OH2") (pin "5") (pinfunction "5_5") (pintype "passive"))
      (node (ref "OH3") (pin "5") (pinfunction "5_5") (pintype "passive"))
      (node (ref "OH4") (pin "5") (pinfunction "5_5") (pintype "passive"))
      (node (ref "OH5") (pin "5") (pinfunction "5_5") (pintype "passive"))
      (node (ref "OH6") (pin "5") (pinfunction "5_5") (pintype "passive"))
      (node (ref "OH7") (pin "5") (pinfunction "5_5") (pintype "passive"))
      (node (ref "OH8") (pin "5") (pinfunction "5_5") (pintype "passive"))
      (node (ref "R24") (pin "1") (pinfunction "1_1") (pintype "passive"))
    )
    (net (code "83") (name "LR_6_MI") (class "Default")
      (node (ref "Q3") (pin "3") (pinfunction "G2_3") (pintype "bidirectional"))
      (node (ref "R25") (pin "2") (pinfunction "2_2") (pintype "passive"))
      (node (ref "U1") (pin "26") (pinfunction "PB0_26") (pintype "bidirectional"))
    )
    (net (code "84") (name "LR_6_MO") (class "Default")
      (node (ref "OH1") (pin "7") (pinfunction "7_7") (pintype "passive"))
      (node (ref "OH2") (pin "7") (pinfunction "7_7") (pintype "passive"))
      (node (ref "OH3") (pin "7") (pinfunction "7_7") (pintype "passive"))
      (node (ref "OH4") (pin "7") (pinfunction "7_7") (pintype "passive"))
      (node (ref "OH5") (pin "7") (pinfunction "7_7") (pintype "passive"))
      (node (ref "OH6") (pin "7") (pinfunction "7_7") (pintype "passive"))
      (node (ref "OH7") (pin "7") (pinfunction "7_7") (pintype "passive"))
      (node (ref "OH8") (pin "7") (pinfunction "7_7") (pintype "passive"))
      (node (ref "R26") (pin "1") (pinfunction "1_1") (pintype "passive"))
    )
    (net (code "85") (name "MIDI_IN") (class "Default")
      (node (ref "R4") (pin "2") (pinfunction "2_2") (pintype "passive"))
      (node (ref "U1") (pin "38") (pinfunction "PC7_38") (pintype "bidirectional"))
      (node (ref "U2") (pin "6") (pinfunction "VO_6") (pintype "output"))
    )
    (net (code "86") (name "MIDI_IN_LED") (class "Default")
      (node (ref "R7") (pin "2") (pinfunction "2_2") (pintype "passive"))
      (node (ref "U1") (pin "43") (pinfunction "PA10_43") (pintype "bidirectional"))
    )
    (net (code "87") (name "MIDI_OUT") (class "Default")
      (node (ref "R12") (pin "2") (pinfunction "2_2") (pintype "passive"))
      (node (ref "U1") (pin "37") (pinfunction "PC6_37") (pintype "bidirectional"))
    )
    (net (code "88") (name "MIDI_OUT_LED") (class "Default")
      (node (ref "R6") (pin "2") (pinfunction "2_2") (pintype "passive"))
      (node (ref "U1") (pin "42") (pinfunction "PA9_42") (pintype "bidirectional"))
    )
    (net (code "89") (name "MISO") (class "Default")
      (node (ref "CONN5") (pin "2") (pinfunction "2_2") (pintype "passive"))
      (node (ref "U1") (pin "52") (pinfunction "PC11_52") (pintype "bidirectional"))
    )
    (net (code "90") (name "MOSI") (class "Default")
      (node (ref "CONN5") (pin "1") (pinfunction "1_1") (pintype "passive"))
      (node (ref "U1") (pin "57") (pinfunction "PB5_57") (pintype "bidirectional"))
    )
    (net (code "91") (name "MUX_COMMON_1") (class "Default")
      (node (ref "U1") (pin "10") (pinfunction "PC2_10") (pintype "bidirectional"))
      (node (ref "U5") (pin "1") (pinfunction "Z_1") (pintype "bidirectional"))
    )
    (net (code "92") (name "MUX_COMMON_2") (class "Default")
      (node (ref "U1") (pin "9") (pinfunction "PC1_9") (pintype "bidirectional"))
      (node (ref "U6") (pin "1") (pinfunction "Z_1") (pintype "bidirectional"))
    )
    (net (code "93") (name "MUX_S0") (class "Default")
      (node (ref "U1") (pin "35") (pinfunction "PB14_35") (pintype "bidirectional"))
      (node (ref "U5") (pin "10") (pinfunction "S0_10") (pintype "input"))
      (node (ref "U6") (pin "10") (pinfunction "S0_10") (pintype "input"))
    )
    (net (code "94") (name "MUX_S1") (class "Default")
      (node (ref "U1") (pin "36") (pinfunction "PB15_36") (pintype "bidirectional"))
      (node (ref "U5") (pin "11") (pinfunction "S1_11") (pintype "input"))
      (node (ref "U6") (pin "11") (pinfunction "S1_11") (pintype "input"))
    )
    (net (code "95") (name "MUX_S2") (class "Default")
      (node (ref "U1") (pin "33") (pinfunction "PB12_33") (pintype "bidirectional"))
      (node (ref "U5") (pin "14") (pinfunction "S2_14") (pintype "input"))
      (node (ref "U6") (pin "14") (pinfunction "S2_14") (pintype "input"))
    )
    (net (code "96") (name "MUX_S3") (class "Default")
      (node (ref "U1") (pin "34") (pinfunction "PB13_34") (pintype "bidirectional"))
      (node (ref "U5") (pin "13") (pinfunction "S3_13") (pintype "input"))
      (node (ref "U6") (pin "13") (pinfunction "S3_13") (pintype "input"))
    )
    (net (code "97") (name "NRST") (class "Default")
      (node (ref "C17") (pin "1") (pinfunction "1_1") (pintype "passive"))
      (node (ref "U1") (pin "7") (pinfunction "NRST_7") (pintype "bidirectional"))
    )
    (net (code "98") (name "Net-(C1-Pad2)") (class "Default")
      (node (ref "C1") (pin "2") (pinfunction "2_2") (pintype "passive"))
      (node (ref "U1") (pin "31") (pinfunction "VCAP_31") (pintype "bidirectional"))
    )
    (net (code "99") (name "Net-(C2-Pad1)") (class "Default")
      (node (ref "C2") (pin "1") (pinfunction "1_1") (pintype "passive"))
      (node (ref "U1") (pin "47") (pinfunction "VCAP_47") (pintype "bidirectional"))
    )
    (net (code "100") (name "Net-(CONN3-Pad4)") (class "Default")
      (node (ref "CONN3") (pin "4") (pinfunction "4_4") (pintype "bidirectional"))
      (node (ref "R5") (pin "1") (pinfunction "1_1") (pintype "passive"))
    )
    (net (code "101") (name "Net-(CONN4-Pad4)") (class "Default")
      (node (ref "CONN4") (pin "4") (pinfunction "4_4") (pintype "bidirectional"))
      (node (ref "R10") (pin "1") (pinfunction "1_1") (pintype "passive"))
    )
    (net (code "102") (name "Net-(CONN4-Pad5)") (class "Default")
      (node (ref "CONN4") (pin "5") (pinfunction "5_5") (pintype "bidirectional"))
      (node (ref "R12") (pin "1") (pinfunction "1_1") (pintype "passive"))
    )
    (net (code "103") (name "Net-(D1-Pad1)") (class "Default")
      (node (ref "D1") (pin "1") (pinfunction "1_1") (pintype "passive"))
      (node (ref "IH1") (pin "2") (pinfunction "2_2") (pintype "passive"))
    )
    (net (code "104") (name "Net-(D1-Pad2)") (class "Default")
      (node (ref "D1") (pin "2") (pinfunction "2_2") (pintype "passive"))
      (node (ref "IH1") (pin "8") (pinfunction "8_8") (pintype "passive"))
    )
    (net (code "105") (name "Net-(D2-Pad1)") (class "Default")
      (node (ref "D2") (pin "1") (pinfunction "1_1") (pintype "passive"))
      (node (ref "IH2") (pin "2") (pinfunction "2_2") (pintype "passive"))
    )
    (net (code "106") (name "Net-(D2-Pad2)") (class "Default")
      (node (ref "D2") (pin "2") (pinfunction "2_2") (pintype "passive"))
      (node (ref "IH2") (pin "8") (pinfunction "8_8") (pintype "passive"))
    )
    (net (code "107") (name "Net-(D3-Pad1)") (class "Default")
      (node (ref "D3") (pin "1") (pinfunction "1_1") (pintype "passive"))
      (node (ref "IH3") (pin "2") (pinfunction "2_2") (pintype "passive"))
    )
    (net (code "108") (name "Net-(D3-Pad2)") (class "Default")
      (node (ref "D3") (pin "2") (pinfunction "2_2") (pintype "passive"))
      (node (ref "IH3") (pin "8") (pinfunction "8_8") (pintype "passive"))
    )
    (net (code "109") (name "Net-(D4-Pad1)") (class "Default")
      (node (ref "D4") (pin "1") (pinfunction "1_1") (pintype "passive"))
      (node (ref "IH4") (pin "2") (pinfunction "2_2") (pintype "passive"))
    )
    (net (code "110") (name "Net-(D4-Pad2)") (class "Default")
      (node (ref "D4") (pin "2") (pinfunction "2_2") (pintype "passive"))
      (node (ref "IH4") (pin "8") (pinfunction "8_8") (pintype "passive"))
    )
    (net (code "111") (name "Net-(D5-Pad1)") (class "Default")
      (node (ref "D5") (pin "1") (pinfunction "1_1") (pintype "passive"))
      (node (ref "IH1") (pin "4") (pinfunction "4_4") (pintype "passive"))
    )
    (net (code "112") (name "Net-(D5-Pad2)") (class "Default")
      (node (ref "D5") (pin "2") (pinfunction "2_2") (pintype "passive"))
      (node (ref "IH1") (pin "6") (pinfunction "6_6") (pintype "passive"))
    )
    (net (code "113") (name "Net-(D6-Pad1)") (class "Default")
      (node (ref "D6") (pin "1") (pinfunction "1_1") (pintype "passive"))
      (node (ref "IH2") (pin "4") (pinfunction "4_4") (pintype "passive"))
    )
    (net (code "114") (name "Net-(D6-Pad2)") (class "Default")
      (node (ref "D6") (pin "2") (pinfunction "2_2") (pintype "passive"))
      (node (ref "IH2") (pin "6") (pinfunction "6_6") (pintype "passive"))
    )
    (net (code "115") (name "Net-(D7-Pad1)") (class "Default")
      (node (ref "D7") (pin "1") (pinfunction "1_1") (pintype "passive"))
      (node (ref "IH3") (pin "4") (pinfunction "4_4") (pintype "passive"))
    )
    (net (code "116") (name "Net-(D7-Pad2)") (class "Default")
      (node (ref "D7") (pin "2") (pinfunction "2_2") (pintype "passive"))
      (node (ref "IH3") (pin "6") (pinfunction "6_6") (pintype "passive"))
    )
    (net (code "117") (name "Net-(D8-Pad1)") (class "Default")
      (node (ref "D8") (pin "1") (pinfunction "1_1") (pintype "passive"))
      (node (ref "IH4") (pin "4") (pinfunction "4_4") (pintype "passive"))
    )
    (net (code "118") (name "Net-(D8-Pad2)") (class "Default")
      (node (ref "D8") (pin "2") (pinfunction "2_2") (pintype "passive"))
      (node (ref "IH4") (pin "6") (pinfunction "6_6") (pintype "passive"))
    )
    (net (code "119") (name "Net-(D9-Pad1)") (class "Default")
      (node (ref "D9") (pin "1") (pinfunction "1_1") (pintype "passive"))
      (node (ref "IH1") (pin "10") (pinfunction "10_10") (pintype "passive"))
    )
    (net (code "120") (name "Net-(D9-Pad2)") (class "Default")
      (node (ref "D9") (pin "2") (pinfunction "2_2") (pintype "passive"))
      (node (ref "IH1") (pin "16") (pinfunction "16_16") (pintype "passive"))
    )
    (net (code "121") (name "Net-(D10-Pad1)") (class "Default")
      (node (ref "D10") (pin "1") (pinfunction "1_1") (pintype "passive"))
      (node (ref "IH2") (pin "10") (pinfunction "10_10") (pintype "passive"))
    )
    (net (code "122") (name "Net-(D10-Pad2)") (class "Default")
      (node (ref "D10") (pin "2") (pinfunction "2_2") (pintype "passive"))
      (node (ref "IH2") (pin "16") (pinfunction "16_16") (pintype "passive"))
    )
    (net (code "123") (name "Net-(D11-Pad1)") (class "Default")
      (node (ref "D11") (pin "1") (pinfunction "1_1") (pintype "passive"))
      (node (ref "IH3") (pin "10") (pinfunction "10_10") (pintype "passive"))
    )
    (net (code "124") (name "Net-(D11-Pad2)") (class "Default")
      (node (ref "D11") (pin "2") (pinfunction "2_2") (pintype "passive"))
      (node (ref "IH3") (pin "16") (pinfunction "16_16") (pintype "passive"))
    )
    (net (code "125") (name "Net-(D12-Pad1)") (class "Default")
      (node (ref "D12") (pin "1") (pinfunction "1_1") (pintype "passive"))
      (node (ref "IH4") (pin "10") (pinfunction "10_10") (pintype "passive"))
    )
    (net (code "126") (name "Net-(D12-Pad2)") (class "Default")
      (node (ref "D12") (pin "2") (pinfunction "2_2") (pintype "passive"))
      (node (ref "IH4") (pin "16") (pinfunction "16_16") (pintype "passive"))
    )
    (net (code "127") (name "Net-(D13-Pad1)") (class "Default")
      (node (ref "D13") (pin "1") (pinfunction "1_1") (pintype "passive"))
      (node (ref "IH1") (pin "12") (pinfunction "12_12") (pintype "passive"))
    )
    (net (code "128") (name "Net-(D13-Pad2)") (class "Default")
      (node (ref "D13") (pin "2") (pinfunction "2_2") (pintype "passive"))
      (node (ref "IH1") (pin "14") (pinfunction "14_14") (pintype "passive"))
    )
    (net (code "129") (name "Net-(D14-Pad1)") (class "Default")
      (node (ref "D14") (pin "1") (pinfunction "1_1") (pintype "passive"))
      (node (ref "IH2") (pin "12") (pinfunction "12_12") (pintype "passive"))
    )
    (net (code "130") (name "Net-(D14-Pad2)") (class "Default")
      (node (ref "D14") (pin "2") (pinfunction "2_2") (pintype "passive"))
      (node (ref "IH2") (pin "14") (pinfunction "14_14") (pintype "passive"))
    )
    (net (code "131") (name "Net-(D15-Pad1)") (class "Default")
      (node (ref "D15") (pin "1") (pinfunction "1_1") (pintype "passive"))
      (node (ref "IH3") (pin "12") (pinfunction "12_12") (pintype "passive"))
    )
    (net (code "132") (name "Net-(D15-Pad2)") (class "Default")
      (node (ref "D15") (pin "2") (pinfunction "2_2") (pintype "passive"))
      (node (ref "IH3") (pin "14") (pinfunction "14_14") (pintype "passive"))
    )
    (net (code "133") (name "Net-(D16-Pad1)") (class "Default")
      (node (ref "D16") (pin "1") (pinfunction "1_1") (pintype "passive"))
      (node (ref "IH4") (pin "12") (pinfunction "12_12") (pintype "passive"))
    )
    (net (code "134") (name "Net-(D16-Pad2)") (class "Default")
      (node (ref "D16") (pin "2") (pinfunction "2_2") (pintype "passive"))
      (node (ref "IH4") (pin "14") (pinfunction "14_14") (pintype "passive"))
    )
    (net (code "135") (name "Net-(D18-Pad1)") (class "Default")
      (node (ref "D18") (pin "1") (pinfunction "1_1") (pintype "passive"))
      (node (ref "IH5") (pin "2") (pinfunction "2_2") (pintype "passive"))
    )
    (net (code "136") (name "Net-(D18-Pad2)") (class "Default")
      (node (ref "D18") (pin "2") (pinfunction "2_2") (pintype "passive"))
      (node (ref "IH5") (pin "8") (pinfunction "8_8") (pintype "passive"))
    )
    (net (code "137") (name "Net-(D19-Pad1)") (class "Default")
      (node (ref "D19") (pin "1") (pinfunction "1_1") (pintype "passive"))
      (node (ref "IH6") (pin "2") (pinfunction "2_2") (pintype "passive"))
    )
    (net (code "138") (name "Net-(D19-Pad2)") (class "Default")
      (node (ref "D19") (pin "2") (pinfunction "2_2") (pintype "passive"))
      (node (ref "IH6") (pin "8") (pinfunction "8_8") (pintype "passive"))
    )
    (net (code "139") (name "Net-(D20-Pad1)") (class "Default")
      (node (ref "D20") (pin "1") (pinfunction "1_1") (pintype "passive"))
      (node (ref "IH7") (pin "2") (pinfunction "2_2") (pintype "passive"))
    )
    (net (code "140") (name "Net-(D20-Pad2)") (class "Default")
      (node (ref "D20") (pin "2") (pinfunction "2_2") (pintype "passive"))
      (node (ref "IH7") (pin "8") (pinfunction "8_8") (pintype "passive"))
    )
    (net (code "141") (name "Net-(D21-Pad1)") (class "Default")
      (node (ref "D21") (pin "1") (pinfunction "1_1") (pintype "passive"))
      (node (ref "IH8") (pin "2") (pinfunction "2_2") (pintype "passive"))
    )
    (net (code "142") (name "Net-(D21-Pad2)") (class "Default")
      (node (ref "D21") (pin "2") (pinfunction "2_2") (pintype "passive"))
      (node (ref "IH8") (pin "8") (pinfunction "8_8") (pintype "passive"))
    )
    (net (code "143") (name "Net-(D22-Pad1)") (class "Default")
      (node (ref "D22") (pin "1") (pinfunction "1_1") (pintype "passive"))
      (node (ref "IH5") (pin "4") (pinfunction "4_4") (pintype "passive"))
    )
    (net (code "144") (name "Net-(D22-Pad2)") (class "Default")
      (node (ref "D22") (pin "2") (pinfunction "2_2") (pintype "passive"))
      (node (ref "IH5") (pin "6") (pinfunction "6_6") (pintype "passive"))
    )
    (net (code "145") (name "Net-(D23-Pad1)") (class "Default")
      (node (ref "D23") (pin "1") (pinfunction "1_1") (pintype "passive"))
      (node (ref "IH6") (pin "4") (pinfunction "4_4") (pintype "passive"))
    )
    (net (code "146") (name "Net-(D23-Pad2)") (class "Default")
      (node (ref "D23") (pin "2") (pinfunction "2_2") (pintype "passive"))
      (node (ref "IH6") (pin "6") (pinfunction "6_6") (pintype "passive"))
    )
    (net (code "147") (name "Net-(D24-Pad1)") (class "Default")
      (node (ref "D24") (pin "1") (pinfunction "1_1") (pintype "passive"))
      (node (ref "IH7") (pin "4") (pinfunction "4_4") (pintype "passive"))
    )
    (net (code "148") (name "Net-(D24-Pad2)") (class "Default")
      (node (ref "D24") (pin "2") (pinfunction "2_2") (pintype "passive"))
      (node (ref "IH7") (pin "6") (pinfunction "6_6") (pintype "passive"))
    )
    (net (code "149") (name "Net-(D25-Pad1)") (class "Default")
      (node (ref "D25") (pin "1") (pinfunction "1_1") (pintype "passive"))
      (node (ref "IH8") (pin "4") (pinfunction "4_4") (pintype "passive"))
    )
    (net (code "150") (name "Net-(D25-Pad2)") (class "Default")
      (node (ref "D25") (pin "2") (pinfunction "2_2") (pintype "passive"))
      (node (ref "IH8") (pin "6") (pinfunction "6_6") (pintype "passive"))
    )
    (net (code "151") (name "Net-(D26-Pad1)") (class "Default")
      (node (ref "D26") (pin "1") (pinfunction "1_1") (pintype "passive"))
      (node (ref "IH5") (pin "10") (pinfunction "10_10") (pintype "passive"))
    )
    (net (code "152") (name "Net-(D26-Pad2)") (class "Default")
      (node (ref "D26") (pin "2") (pinfunction "2_2") (pintype "passive"))
      (node (ref "IH5") (pin "16") (pinfunction "16_16") (pintype "passive"))
    )
    (net (code "153") (name "Net-(D27-Pad1)") (class "Default")
      (node (ref "D27") (pin "1") (pinfunction "1_1") (pintype "passive"))
      (node (ref "IH6") (pin "10") (pinfunction "10_10") (pintype "passive"))
    )
    (net (code "154") (name "Net-(D27-Pad2)") (class "Default")
      (node (ref "D27") (pin "2") (pinfunction "2_2") (pintype "passive"))
      (node (ref "IH6") (pin "16") (pinfunction "16_16") (pintype "passive"))
    )
    (net (code "155") (name "Net-(D28-Pad1)") (class "Default")
      (node (ref "D28") (pin "1") (pinfunction "1_1") (pintype "passive"))
      (node (ref "IH7") (pin "10") (pinfunction "10_10") (pintype "passive"))
    )
    (net (code "156") (name "Net-(D28-Pad2)") (class "Default")
      (node (ref "D28") (pin "2") (pinfunction "2_2") (pintype "passive"))
      (node (ref "IH7") (pin "16") (pinfunction "16_16") (pintype "passive"))
    )
    (net (code "157") (name "Net-(D29-Pad1)") (class "Default")
      (node (ref "D29") (pin "1") (pinfunction "1_1") (pintype "passive"))
      (node (ref "IH8") (pin "10") (pinfunction "10_10") (pintype "passive"))
    )
    (net (code "158") (name "Net-(D29-Pad2)") (class "Default")
      (node (ref "D29") (pin "2") (pinfunction "2_2") (pintype "passive"))
      (node (ref "IH8") (pin "16") (pinfunction "16_16") (pintype "passive"))
    )
    (net (code "159") (name "Net-(D30-Pad1)") (class "Default")
      (node (ref "D30") (pin "1") (pinfunction "1_1") (pintype "passive"))
      (node (ref "IH5") (pin "12") (pinfunction "12_12") (pintype "passive"))
    )
    (net (code "160") (name "Net-(D30-Pad2)") (class "Default")
      (node (ref "D30") (pin "2") (pinfunction "2_2") (pintype "passive"))
      (node (ref "IH5") (pin "14") (pinfunction "14_14") (pintype "passive"))
    )
    (net (code "161") (name "Net-(D31-Pad1)") (class "Default")
      (node (ref "D31") (pin "1") (pinfunction "1_1") (pintype "passive"))
      (node (ref "IH6") (pin "12") (pinfunction "12_12") (pintype "passive"))
    )
    (net (code "162") (name "Net-(D31-Pad2)") (class "Default")
      (node (ref "D31") (pin "2") (pinfunction "2_2") (pintype "passive"))
      (node (ref "IH6") (pin "14") (pinfunction "14_14") (pintype "passive"))
    )
    (net (code "163") (name "Net-(D32-Pad1)") (class "Default")
      (node (ref "D32") (pin "1") (pinfunction "1_1") (pintype "passive"))
      (node (ref "IH7") (pin "12") (pinfunction "12_12") (pintype "passive"))
    )
    (net (code "164") (name "Net-(D32-Pad2)") (class "Default")
      (node (ref "D32") (pin "2") (pinfunction "2_2") (pintype "passive"))
      (node (ref "IH7") (pin "14") (pinfunction "14_14") (pintype "passive"))
    )
    (net (code "165") (name "Net-(D33-Pad1)") (class "Default")
      (node (ref "D33") (pin "1") (pinfunction "1_1") (pintype "passive"))
      (node (ref "IH8") (pin "12") (pinfunction "12_12") (pintype "passive"))
    )
    (net (code "166") (name "Net-(D33-Pad2)") (class "Default")
      (node (ref "D33") (pin "2") (pinfunction "2_2") (pintype "passive"))
      (node (ref "IH8") (pin "14") (pinfunction "14_14") (pintype "passive"))
    )
    (net (code "167") (name "Net-(D35-PadA)") (class "Default")
      (node (ref "D35") (pin "A") (pinfunction "A_A") (pintype "passive"))
      (node (ref "R6") (pin "1") (pinfunction "1_1") (pintype "passive"))
    )
    (net (code "168") (name "Net-(D36-PadA)") (class "Default")
      (node (ref "D36") (pin "A") (pinfunction "A_A") (pintype "passive"))
      (node (ref "R7") (pin "1") (pinfunction "1_1") (pintype "passive"))
    )
    (net (code "169") (name "Net-(D37-PadA)") (class "Default")
      (node (ref "D37") (pin "A") (pinfunction "A_A") (pintype "passive"))
      (node (ref "R8") (pin "2") (pinfunction "2_2") (pintype "passive"))
    )
    (net (code "170") (name "Net-(Q1-D1)") (class "Default")
      (node (ref "Q1") (pin "6") (pinfunction "D1_6") (pintype "bidirectional"))
      (node (ref "R20") (pin "2") (pinfunction "2_2") (pintype "passive"))
    )
    (net (code "171") (name "Net-(Q1-D2)") (class "Default")
      (node (ref "Q1") (pin "4") (pinfunction "D2_4") (pintype "bidirectional"))
      (node (ref "R22") (pin "1") (pinfunction "1_1") (pintype "passive"))
    )
    (net (code "172") (name "Net-(Q2-D1)") (class "Default")
      (node (ref "Q2") (pin "6") (pinfunction "D1_6") (pintype "bidirectional"))
      (node (ref "R28") (pin "2") (pinfunction "2_2") (pintype "passive"))
    )
    (net (code "173") (name "Net-(Q2-D2)") (class "Default")
      (node (ref "Q2") (pin "4") (pinfunction "D2_4") (pintype "bidirectional"))
      (node (ref "R30") (pin "2") (pinfunction "2_2") (pintype "passive"))
    )
    (net (code "174") (name "Net-(Q3-D1)") (class "Default")
      (node (ref "Q3") (pin "6") (pinfunction "D1_6") (pintype "bidirectional"))
      (node (ref "R24") (pin "2") (pinfunction "2_2") (pintype "passive"))
    )
    (net (code "175") (name "Net-(Q3-D2)") (class "Default")
      (node (ref "Q3") (pin "4") (pinfunction "D2_4") (pintype "bidirectional"))
      (node (ref "R26") (pin "2") (pinfunction "2_2") (pintype "passive"))
    )
    (net (code "176") (name "Net-(U2-A)") (class "Default")
      (node (ref "D34") (pin "2") (pinfunction "2_2") (pintype "passive"))
      (node (ref "R5") (pin "2") (pinfunction "2_2") (pintype "passive"))
      (node (ref "U2") (pin "2") (pinfunction "A_2") (pintype "passive"))
    )
    (net (code "177") (name "Net-(U2-C)") (class "Default")
      (node (ref "CONN3") (pin "5") (pinfunction "5_5") (pintype "bidirectional"))
      (node (ref "D34") (pin "3") (pinfunction "3_3") (pintype "passive"))
      (node (ref "U2") (pin "3") (pinfunction "C_3") (pintype "passive"))
    )
    (net (code "178") (name "Net-(U7-Y0)") (class "Default")
      (node (ref "U7") (pin "15") (pinfunction "Y0_15") (pintype "output"))
      (node (ref "U8") (pin "1") (pinfunction "1B_1") (pintype "input"))
    )
    (net (code "179") (name "Net-(U7-Y1)") (class "Default")
      (node (ref "U7") (pin "14") (pinfunction "Y1_14") (pintype "output"))
      (node (ref "U8") (pin "2") (pinfunction "2B_2") (pintype "input"))
    )
    (net (code "180") (name "Net-(U7-Y2)") (class "Default")
      (node (ref "U7") (pin "13") (pinfunction "Y2_13") (pintype "output"))
      (node (ref "U8") (pin "3") (pinfunction "3B_3") (pintype "input"))
    )
    (net (code "181") (name "Net-(U7-Y3)") (class "Default")
      (node (ref "U7") (pin "12") (pinfunction "Y3_12") (pintype "output"))
      (node (ref "U8") (pin "4") (pinfunction "4B_4") (pintype "input"))
    )
    (net (code "182") (name "Net-(U7-Y4)") (class "Default")
      (node (ref "U7") (pin "11") (pinfunction "Y4_11") (pintype "output"))
      (node (ref "U8") (pin "5") (pinfunction "5B_5") (pintype "input"))
    )
    (net (code "183") (name "Net-(U7-Y5)") (class "Default")
      (node (ref "U7") (pin "10") (pinfunction "Y5_10") (pintype "output"))
      (node (ref "U8") (pin "6") (pinfunction "6B_6") (pintype "input"))
    )
    (net (code "184") (name "Net-(U7-Y6)") (class "Default")
      (node (ref "U7") (pin "9") (pinfunction "Y6_9") (pintype "output"))
      (node (ref "U8") (pin "7") (pinfunction "7B_7") (pintype "input"))
    )
    (net (code "185") (name "Net-(U7-Y7)") (class "Default")
      (node (ref "U7") (pin "7") (pinfunction "Y7_7") (pintype "output"))
      (node (ref "U8") (pin "8") (pinfunction "8B_8") (pintype "input"))
    )
    (net (code "186") (name "OSC_IN") (class "Default")
      (node (ref "C23") (pin "1") (pinfunction "1_1") (pintype "passive"))
      (node (ref "U1") (pin "5") (pinfunction "PH0_5") (pintype "bidirectional"))
      (node (ref "Y1") (pin "1") (pinfunction "1_1") (pintype "passive"))
    )
    (net (code "187") (name "OSC_OUT") (class "Default")
      (node (ref "C24") (pin "1") (pinfunction "1_1") (pintype "passive"))
      (node (ref "U1") (pin "6") (pinfunction "PH1_6") (pintype "bidirectional"))
      (node (ref "Y1") (pin "3") (pinfunction "2_3") (pintype "passive"))
    )
    (net (code "188") (name "SCK") (class "Default")
      (node (ref "CONN5") (pin "3") (pinfunction "3_3") (pintype "passive"))
      (node (ref "U1") (pin "51") (pinfunction "PC10_51") (pintype "bidirectional"))
    )
    (net (code "189") (name "SCL") (class "Default")
      (node (ref "CONN6") (pin "2") (pinfunction "2_2") (pintype "passive"))
      (node (ref "U1") (pin "58") (pinfunction "PB6_58") (pintype "bidirectional"))
    )
    (net (code "190") (name "SDA") (class "Default")
      (node (ref "CONN6") (pin "1") (pinfunction "1_1") (pintype "passive"))
      (node (ref "U1") (pin "59") (pinfunction "PB7_59") (pintype "bidirectional"))
    )
    (net (code "191") (name "SWDCLK") (class "Default")
      (node (ref "CONN8") (pin "2") (pinfunction "2_2") (pintype "passive"))
      (node (ref "U1") (pin "49") (pinfunction "PA14_49") (pintype "bidirectional"))
    )
    (net (code "192") (name "SWDIO") (class "Default")
      (node (ref "CONN8") (pin "1") (pinfunction "1_1") (pintype "passive"))
      (node (ref "U1") (pin "46") (pinfunction "PA13_46") (pintype "bidirectional"))
    )
    (net (code "193") (name "UART_RX") (class "Default")
      (node (ref "CONN7") (pin "1") (pinfunction "1_1") (pintype "passive"))
      (node (ref "U1") (pin "54") (pinfunction "PD2_54") (pintype "bidirectional"))
    )
    (net (code "194") (name "UART_TX") (class "Default")
      (node (ref "CONN7") (pin "2") (pinfunction "2_2") (pintype "passive"))
      (node (ref "U1") (pin "53") (pinfunction "PC12_53") (pintype "bidirectional"))
    )
    (net (code "195") (name "USB_SHIELD") (class "Default")
      (node (ref "CONN1") (pin "S1") (pinfunction "S_S1") (pintype "passive"))
      (node (ref "CONN1") (pin "S2") (pinfunction "S_S2") (pintype "passive"))
      (node (ref "L1") (pin "2") (pinfunction "2_2") (pintype "passive"))
    )
    (net (code "196") (name "unconnected-(CONN3-Pad1)") (class "Default")
      (node (ref "CONN3") (pin "1") (pinfunction "1_1") (pintype "bidirectional"))
    )
    (net (code "197") (name "unconnected-(CONN3-Pad2)") (class "Default")
      (node (ref "CONN3") (pin "2") (pinfunction "2_2") (pintype "passive"))
    )
    (net (code "198") (name "unconnected-(CONN3-Pad3)") (class "Default")
      (node (ref "CONN3") (pin "3") (pinfunction "3_3") (pintype "bidirectional"))
    )
    (net (code "199") (name "unconnected-(CONN4-Pad1)") (class "Default")
      (node (ref "CONN4") (pin "1") (pinfunction "1_1") (pintype "bidirectional"))
    )
    (net (code "200") (name "unconnected-(CONN4-Pad3)") (class "Default")
      (node (ref "CONN4") (pin "3") (pinfunction "3_3") (pintype "bidirectional"))
    )
    (net (code "201") (name "unconnected-(D34-Pad1)") (class "Default")
      (node (ref "D34") (pin "1") (pinfunction "1_1") (pintype "passive"))
    )
    (net (code "202") (name "unconnected-(U1-PA15-Pad50)") (class "Default")
      (node (ref "U1") (pin "50") (pinfunction "PA15_50") (pintype "bidirectional"))
    )
    (net (code "203") (name "unconnected-(U1-PB3-Pad55)") (class "Default")
      (node (ref "U1") (pin "55") (pinfunction "PB3_55") (pintype "bidirectional"))
    )
    (net (code "204") (name "unconnected-(U1-PC0-Pad8)") (class "Default")
      (node (ref "U1") (pin "8") (pinfunction "PC0_8") (pintype "bidirectional"))
    )
    (net (code "205") (name "unconnected-(U1-PC3-Pad11)") (class "Default")
      (node (ref "U1") (pin "11") (pinfunction "PC3_11") (pintype "bidirectional"))
    )
    (net (code "206") (name "unconnected-(U1-PC13-Pad2)") (class "Default")
      (node (ref "U1") (pin "2") (pinfunction "PC13_2") (pintype "bidirectional"))
    )
    (net (code "207") (name "unconnected-(U1-PC14-Pad3)") (class "Default")
      (node (ref "U1") (pin "3") (pinfunction "PC14_3") (pintype "bidirectional"))
    )
    (net (code "208") (name "unconnected-(U1-PC15-Pad4)") (class "Default")
      (node (ref "U1") (pin "4") (pinfunction "PC15_4") (pintype "bidirectional"))
    )
    (net (code "209") (name "unconnected-(VR1-NC-Pad4)") (class "Default")
      (node (ref "VR1") (pin "4") (pinfunction "NC_4") (pintype "no_connect"))
    )
  )
)
